# PICO_LCD.net
KiCad netlist of a schematic drawn in Altium Designer
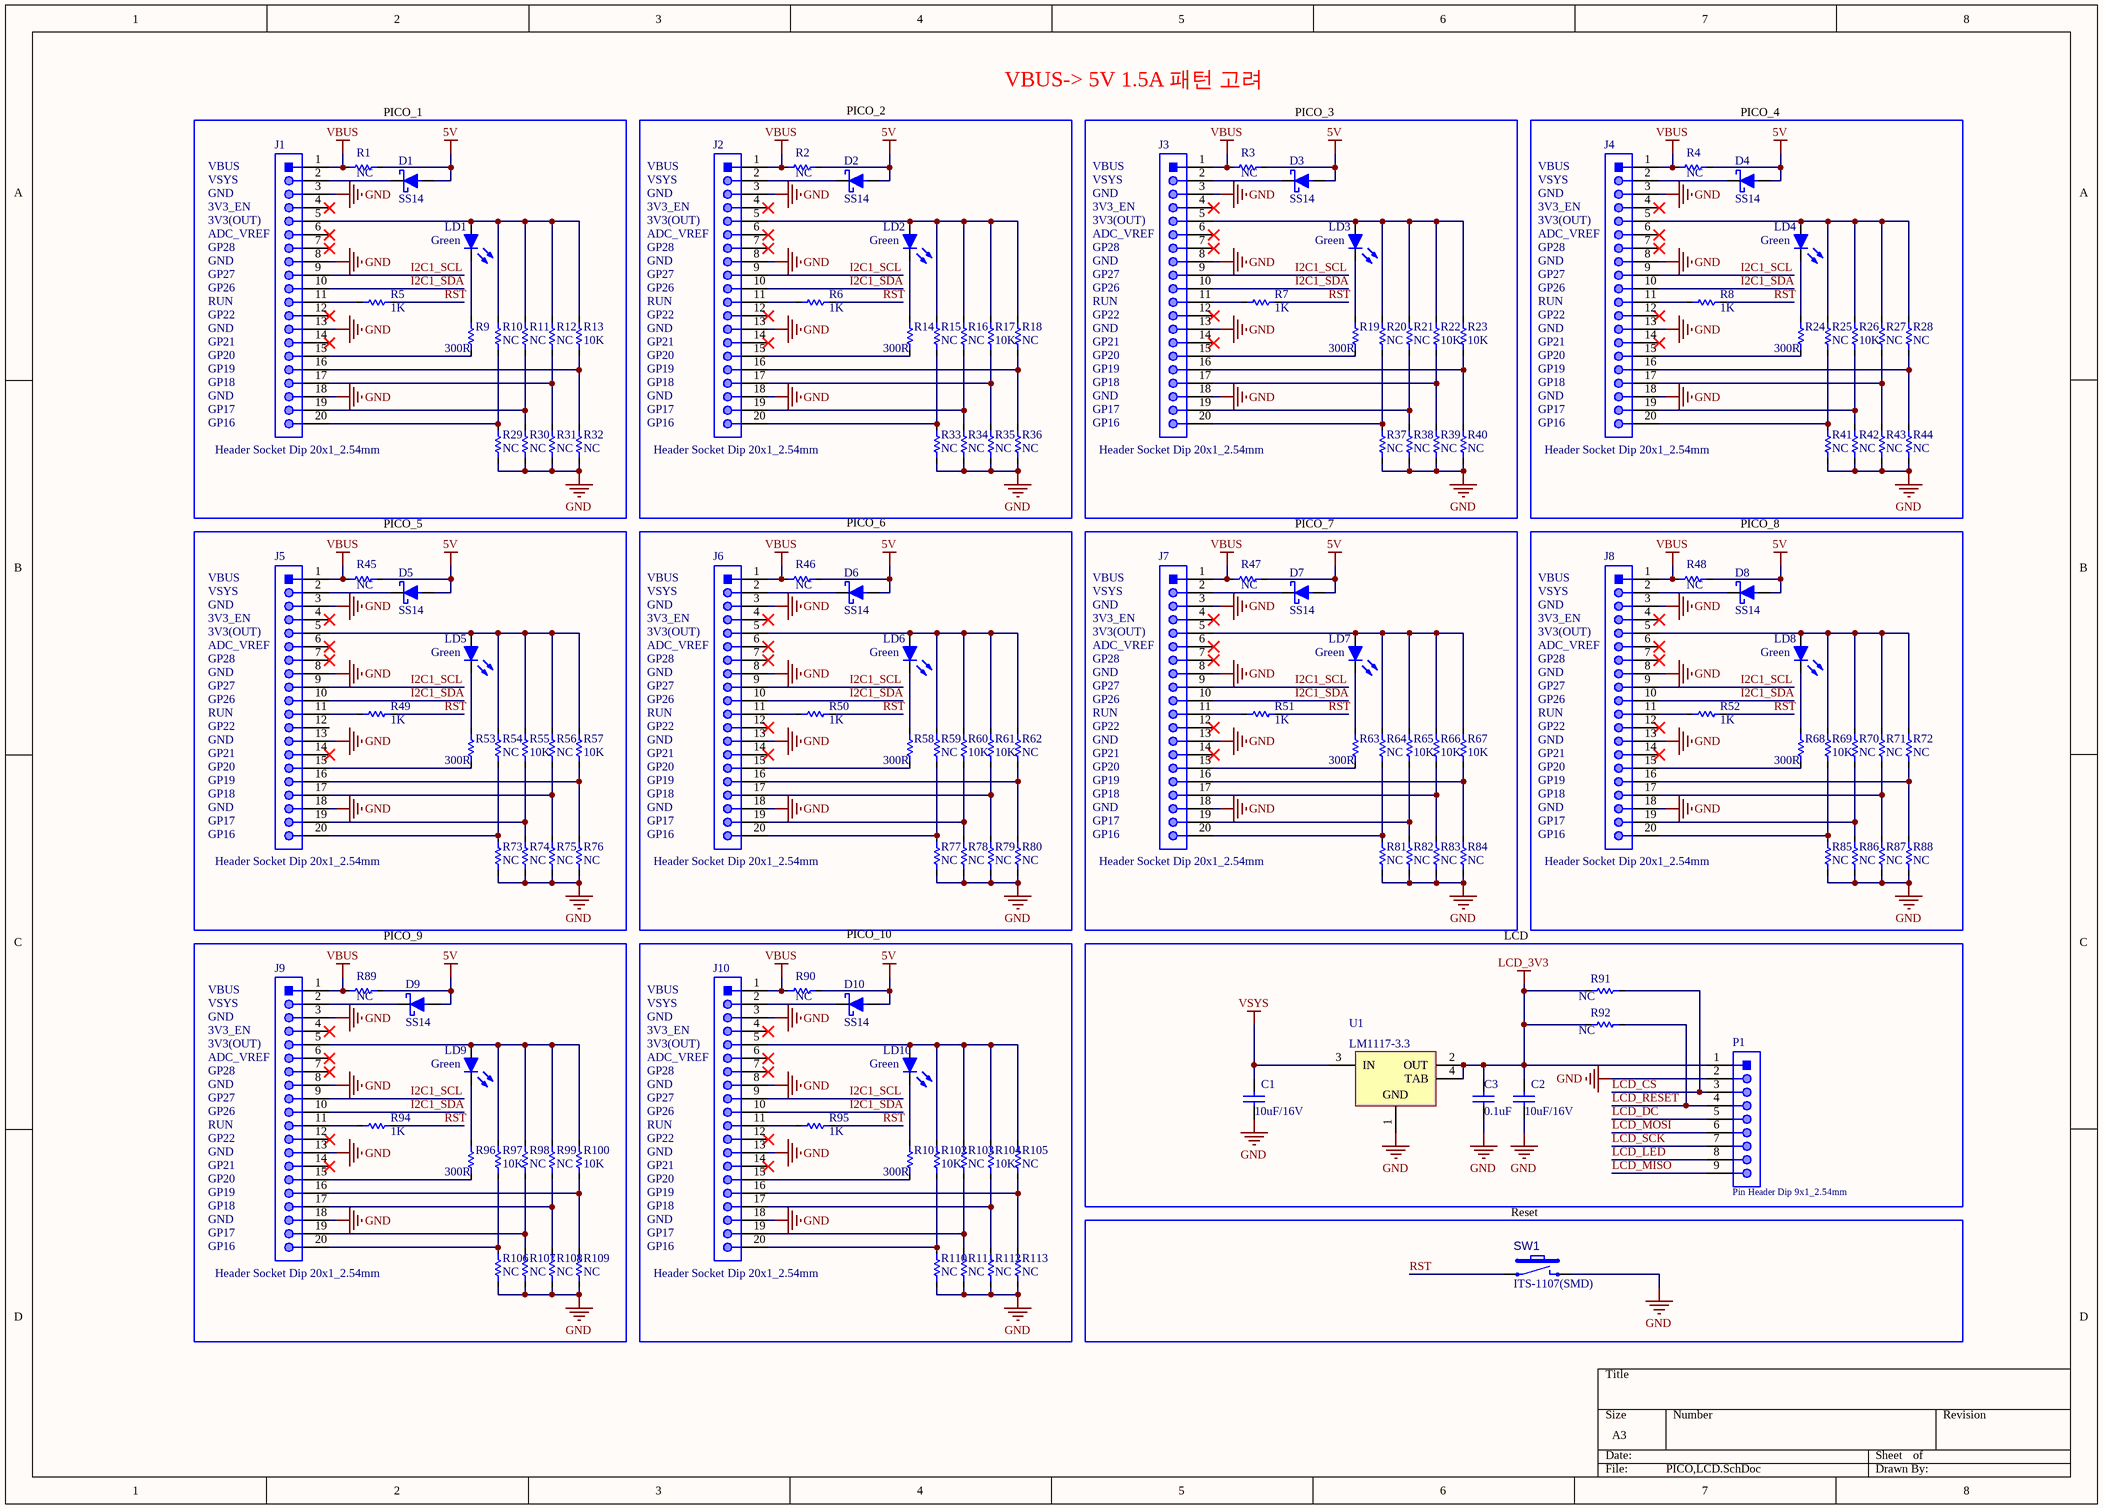
[diagram p0: PICO,LCD.SchDoc]

(export (version "E")
  (design (tool "Eeschema 10.0.6"))
  (components
    (comp (ref "C1")
      (value "10uF/16V")
      (footprint "CAP-0805")
      (description "MLCC-0805(2012)")
      (libsource (lib "Jaden_Lib") (part "CAP-0805"))
    )
    (comp (ref "C2")
      (value "10uF/16V")
      (footprint "CAP-0805")
      (description "MLCC-0805(2012)")
      (libsource (lib "Jaden_Lib") (part "CAP-0805"))
    )
    (comp (ref "C3")
      (value "0.1uF")
      (footprint "CAP-0603")
      (description "MLCC-0603(1608)")
      (libsource (lib "Jaden_Lib") (part "CAP-0603"))
    )
    (comp (ref "D1")
      (value "SS14")
      (footprint "DO-214AC/SMA")
      (description "DIODE SCHOTTKY 40V 1A SMA")
      (fields
        (field (name "MANUFACTURER") "ON Semiconductor")
        (field (name "OCTOPART") "https://octopart.com/ss14-on+semiconductor-29205033")
      )
      (libsource (lib "Jaden_Lib") (part "DIODE-Shottky SMA(DO-214AC)"))
    )
    (comp (ref "D2")
      (value "SS14")
      (footprint "DO-214AC/SMA")
      (description "DIODE SCHOTTKY 40V 1A SMA")
      (fields
        (field (name "MANUFACTURER") "ON Semiconductor")
        (field (name "OCTOPART") "https://octopart.com/ss14-on+semiconductor-29205033")
      )
      (libsource (lib "Jaden_Lib") (part "DIODE-Shottky SMA(DO-214AC)"))
    )
    (comp (ref "D3")
      (value "SS14")
      (footprint "DO-214AC/SMA")
      (description "DIODE SCHOTTKY 40V 1A SMA")
      (fields
        (field (name "MANUFACTURER") "ON Semiconductor")
        (field (name "OCTOPART") "https://octopart.com/ss14-on+semiconductor-29205033")
      )
      (libsource (lib "Jaden_Lib") (part "DIODE-Shottky SMA(DO-214AC)"))
    )
    (comp (ref "D4")
      (value "SS14")
      (footprint "DO-214AC/SMA")
      (description "DIODE SCHOTTKY 40V 1A SMA")
      (fields
        (field (name "MANUFACTURER") "ON Semiconductor")
        (field (name "OCTOPART") "https://octopart.com/ss14-on+semiconductor-29205033")
      )
      (libsource (lib "Jaden_Lib") (part "DIODE-Shottky SMA(DO-214AC)"))
    )
    (comp (ref "D5")
      (value "SS14")
      (footprint "DO-214AC/SMA")
      (description "DIODE SCHOTTKY 40V 1A SMA")
      (fields
        (field (name "MANUFACTURER") "ON Semiconductor")
        (field (name "OCTOPART") "https://octopart.com/ss14-on+semiconductor-29205033")
      )
      (libsource (lib "Jaden_Lib") (part "DIODE-Shottky SMA(DO-214AC)"))
    )
    (comp (ref "D6")
      (value "SS14")
      (footprint "DO-214AC/SMA")
      (description "DIODE SCHOTTKY 40V 1A SMA")
      (fields
        (field (name "MANUFACTURER") "ON Semiconductor")
        (field (name "OCTOPART") "https://octopart.com/ss14-on+semiconductor-29205033")
      )
      (libsource (lib "Jaden_Lib") (part "DIODE-Shottky SMA(DO-214AC)"))
    )
    (comp (ref "D7")
      (value "SS14")
      (footprint "DO-214AC/SMA")
      (description "DIODE SCHOTTKY 40V 1A SMA")
      (fields
        (field (name "MANUFACTURER") "ON Semiconductor")
        (field (name "OCTOPART") "https://octopart.com/ss14-on+semiconductor-29205033")
      )
      (libsource (lib "Jaden_Lib") (part "DIODE-Shottky SMA(DO-214AC)"))
    )
    (comp (ref "D8")
      (value "SS14")
      (footprint "DO-214AC/SMA")
      (description "DIODE SCHOTTKY 40V 1A SMA")
      (fields
        (field (name "MANUFACTURER") "ON Semiconductor")
        (field (name "OCTOPART") "https://octopart.com/ss14-on+semiconductor-29205033")
      )
      (libsource (lib "Jaden_Lib") (part "DIODE-Shottky SMA(DO-214AC)"))
    )
    (comp (ref "D9")
      (value "SS14")
      (footprint "DO-214AC/SMA")
      (description "DIODE SCHOTTKY 40V 1A SMA")
      (fields
        (field (name "MANUFACTURER") "ON Semiconductor")
        (field (name "OCTOPART") "https://octopart.com/ss14-on+semiconductor-29205033")
      )
      (libsource (lib "Jaden_Lib") (part "DIODE-Shottky SMA(DO-214AC)"))
    )
    (comp (ref "D10")
      (value "SS14")
      (footprint "DO-214AC/SMA")
      (description "DIODE SCHOTTKY 40V 1A SMA")
      (fields
        (field (name "MANUFACTURER") "ON Semiconductor")
        (field (name "OCTOPART") "https://octopart.com/ss14-on+semiconductor-29205033")
      )
      (libsource (lib "Jaden_Lib") (part "DIODE-Shottky SMA(DO-214AC)"))
    )
    (comp (ref "J1")
      (value "Header Socket Dip 20x1_2.54mm")
      (footprint "IDC-1X20(SOCKET)")
      (description "THT Vertical Header Socket WR-PHD, Pitch 2.54 mm, Single Row, 20 pins")
      (fields
        (field (name "MANUFACTURER_PART_NUMBER") "M20-7822046")
        (field (name "MOUSER PART NUMBER") "855-M20-7822046")
      )
      (libsource (lib "Jaden_Lib") (part "Header Socket 20x1_2.54mm"))
    )
    (comp (ref "J2")
      (value "Header Socket Dip 20x1_2.54mm")
      (footprint "IDC-1X20(SOCKET)")
      (description "THT Vertical Header Socket WR-PHD, Pitch 2.54 mm, Single Row, 20 pins")
      (fields
        (field (name "MANUFACTURER_PART_NUMBER") "M20-7822046")
        (field (name "MOUSER PART NUMBER") "855-M20-7822046")
      )
      (libsource (lib "Jaden_Lib") (part "Header Socket 20x1_2.54mm"))
    )
    (comp (ref "J3")
      (value "Header Socket Dip 20x1_2.54mm")
      (footprint "IDC-1X20(SOCKET)")
      (description "THT Vertical Header Socket WR-PHD, Pitch 2.54 mm, Single Row, 20 pins")
      (fields
        (field (name "MANUFACTURER_PART_NUMBER") "M20-7822046")
        (field (name "MOUSER PART NUMBER") "855-M20-7822046")
      )
      (libsource (lib "Jaden_Lib") (part "Header Socket 20x1_2.54mm"))
    )
    (comp (ref "J4")
      (value "Header Socket Dip 20x1_2.54mm")
      (footprint "IDC-1X20(SOCKET)")
      (description "THT Vertical Header Socket WR-PHD, Pitch 2.54 mm, Single Row, 20 pins")
      (fields
        (field (name "MANUFACTURER_PART_NUMBER") "M20-7822046")
        (field (name "MOUSER PART NUMBER") "855-M20-7822046")
      )
      (libsource (lib "Jaden_Lib") (part "Header Socket 20x1_2.54mm"))
    )
    (comp (ref "J5")
      (value "Header Socket Dip 20x1_2.54mm")
      (footprint "IDC-1X20(SOCKET)")
      (description "THT Vertical Header Socket WR-PHD, Pitch 2.54 mm, Single Row, 20 pins")
      (fields
        (field (name "MANUFACTURER_PART_NUMBER") "M20-7822046")
        (field (name "MOUSER PART NUMBER") "855-M20-7822046")
      )
      (libsource (lib "Jaden_Lib") (part "Header Socket 20x1_2.54mm"))
    )
    (comp (ref "J6")
      (value "Header Socket Dip 20x1_2.54mm")
      (footprint "IDC-1X20(SOCKET)")
      (description "THT Vertical Header Socket WR-PHD, Pitch 2.54 mm, Single Row, 20 pins")
      (fields
        (field (name "MANUFACTURER_PART_NUMBER") "M20-7822046")
        (field (name "MOUSER PART NUMBER") "855-M20-7822046")
      )
      (libsource (lib "Jaden_Lib") (part "Header Socket 20x1_2.54mm"))
    )
    (comp (ref "J7")
      (value "Header Socket Dip 20x1_2.54mm")
      (footprint "IDC-1X20(SOCKET)")
      (description "THT Vertical Header Socket WR-PHD, Pitch 2.54 mm, Single Row, 20 pins")
      (fields
        (field (name "MANUFACTURER_PART_NUMBER") "M20-7822046")
        (field (name "MOUSER PART NUMBER") "855-M20-7822046")
      )
      (libsource (lib "Jaden_Lib") (part "Header Socket 20x1_2.54mm"))
    )
    (comp (ref "J8")
      (value "Header Socket Dip 20x1_2.54mm")
      (footprint "IDC-1X20(SOCKET)")
      (description "THT Vertical Header Socket WR-PHD, Pitch 2.54 mm, Single Row, 20 pins")
      (fields
        (field (name "MANUFACTURER_PART_NUMBER") "M20-7822046")
        (field (name "MOUSER PART NUMBER") "855-M20-7822046")
      )
      (libsource (lib "Jaden_Lib") (part "Header Socket 20x1_2.54mm"))
    )
    (comp (ref "J9")
      (value "Header Socket Dip 20x1_2.54mm")
      (footprint "IDC-1X20(SOCKET)")
      (description "THT Vertical Header Socket WR-PHD, Pitch 2.54 mm, Single Row, 20 pins")
      (fields
        (field (name "MANUFACTURER_PART_NUMBER") "M20-7822046")
        (field (name "MOUSER PART NUMBER") "855-M20-7822046")
      )
      (libsource (lib "Jaden_Lib") (part "Header Socket 20x1_2.54mm"))
    )
    (comp (ref "J10")
      (value "Header Socket Dip 20x1_2.54mm")
      (footprint "IDC-1X20(SOCKET)")
      (description "THT Vertical Header Socket WR-PHD, Pitch 2.54 mm, Single Row, 20 pins")
      (fields
        (field (name "MANUFACTURER_PART_NUMBER") "M20-7822046")
        (field (name "MOUSER PART NUMBER") "855-M20-7822046")
      )
      (libsource (lib "Jaden_Lib") (part "Header Socket 20x1_2.54mm"))
    )
    (comp (ref "LD1")
      (value "Green")
      (footprint "LED-0603-GREEN")
      (description "LED-0603")
      (libsource (lib "Jaden_Lib") (part "GREEN LED-0603"))
    )
    (comp (ref "LD2")
      (value "Green")
      (footprint "LED-0603-GREEN")
      (description "LED-0603")
      (libsource (lib "Jaden_Lib") (part "GREEN LED-0603"))
    )
    (comp (ref "LD3")
      (value "Green")
      (footprint "LED-0603-GREEN")
      (description "LED-0603")
      (libsource (lib "Jaden_Lib") (part "GREEN LED-0603"))
    )
    (comp (ref "LD4")
      (value "Green")
      (footprint "LED-0603-GREEN")
      (description "LED-0603")
      (libsource (lib "Jaden_Lib") (part "GREEN LED-0603"))
    )
    (comp (ref "LD5")
      (value "Green")
      (footprint "LED-0603-GREEN")
      (description "LED-0603")
      (libsource (lib "Jaden_Lib") (part "GREEN LED-0603"))
    )
    (comp (ref "LD6")
      (value "Green")
      (footprint "LED-0603-GREEN")
      (description "LED-0603")
      (libsource (lib "Jaden_Lib") (part "GREEN LED-0603"))
    )
    (comp (ref "LD7")
      (value "Green")
      (footprint "LED-0603-GREEN")
      (description "LED-0603")
      (libsource (lib "Jaden_Lib") (part "GREEN LED-0603"))
    )
    (comp (ref "LD8")
      (value "Green")
      (footprint "LED-0603-GREEN")
      (description "LED-0603")
      (libsource (lib "Jaden_Lib") (part "GREEN LED-0603"))
    )
    (comp (ref "LD9")
      (value "Green")
      (footprint "LED-0603-GREEN")
      (description "LED-0603")
      (libsource (lib "Jaden_Lib") (part "GREEN LED-0603"))
    )
    (comp (ref "LD10")
      (value "Green")
      (footprint "LED-0603-GREEN")
      (description "LED-0603")
      (libsource (lib "Jaden_Lib") (part "GREEN LED-0603"))
    )
    (comp (ref "P1")
      (value "Pin Header Dip 9x1_2.54mm")
      (footprint "LCD(PIN HEADER9X1_2.54)")
      (description "THT Vertical Pin Header WR-PHD, Pitch 2.54 mm, Single Row, 9 pins")
      (fields
        (field (name "PART NUMBER") "61300911121")
        (field (name "MANUFACTURER") "Wurth Elektronik")
        (field (name "PUBLISHER") "WurthElektronik")
      )
      (libsource (lib "Jaden_Lib") (part "Pin Header 9x1_2.54mm"))
    )
    (comp (ref "R1")
      (value "NC")
      (footprint "RES-0603")
      (description "Chip Resistor 0603(1608)")
      (fields (field (name "TOLERANCE") "1%") (field (name "MANUFACTURER") "Yageo"))
      (libsource (lib "Jaden_Lib") (part "RES-0603"))
    )
    (comp (ref "R2")
      (value "NC")
      (footprint "RES-0603")
      (description "Chip Resistor 0603(1608)")
      (fields (field (name "TOLERANCE") "1%") (field (name "MANUFACTURER") "Yageo"))
      (libsource (lib "Jaden_Lib") (part "RES-0603"))
    )
    (comp (ref "R3")
      (value "NC")
      (footprint "RES-0603")
      (description "Chip Resistor 0603(1608)")
      (fields (field (name "TOLERANCE") "1%") (field (name "MANUFACTURER") "Yageo"))
      (libsource (lib "Jaden_Lib") (part "RES-0603"))
    )
    (comp (ref "R4")
      (value "NC")
      (footprint "RES-0603")
      (description "Chip Resistor 0603(1608)")
      (fields (field (name "TOLERANCE") "1%") (field (name "MANUFACTURER") "Yageo"))
      (libsource (lib "Jaden_Lib") (part "RES-0603"))
    )
    (comp (ref "R5")
      (value "1K")
      (footprint "RES-0603")
      (description "Chip Resistor 0603(1608)")
      (fields (field (name "TOLERANCE") "1%") (field (name "MANUFACTURER") "Yageo"))
      (libsource (lib "Jaden_Lib") (part "RES-0603"))
    )
    (comp (ref "R6")
      (value "1K")
      (footprint "RES-0603")
      (description "Chip Resistor 0603(1608)")
      (fields (field (name "TOLERANCE") "1%") (field (name "MANUFACTURER") "Yageo"))
      (libsource (lib "Jaden_Lib") (part "RES-0603"))
    )
    (comp (ref "R7")
      (value "1K")
      (footprint "RES-0603")
      (description "Chip Resistor 0603(1608)")
      (fields (field (name "TOLERANCE") "1%") (field (name "MANUFACTURER") "Yageo"))
      (libsource (lib "Jaden_Lib") (part "RES-0603"))
    )
    (comp (ref "R8")
      (value "1K")
      (footprint "RES-0603")
      (description "Chip Resistor 0603(1608)")
      (fields (field (name "TOLERANCE") "1%") (field (name "MANUFACTURER") "Yageo"))
      (libsource (lib "Jaden_Lib") (part "RES-0603"))
    )
    (comp (ref "R9")
      (value "300R")
      (footprint "RES-0603")
      (description "Chip Resistor 0603(1608)")
      (fields (field (name "TOLERANCE") "1%") (field (name "MANUFACTURER") "Yageo"))
      (libsource (lib "Jaden_Lib") (part "RES-0603"))
    )
    (comp (ref "R10")
      (value "NC")
      (footprint "RES-0603")
      (description "Chip Resistor 0603(1608)")
      (fields (field (name "TOLERANCE") "1%") (field (name "MANUFACTURER") "Yageo"))
      (libsource (lib "Jaden_Lib") (part "RES-0603"))
    )
    (comp (ref "R11")
      (value "NC")
      (footprint "RES-0603")
      (description "Chip Resistor 0603(1608)")
      (fields (field (name "TOLERANCE") "1%") (field (name "MANUFACTURER") "Yageo"))
      (libsource (lib "Jaden_Lib") (part "RES-0603"))
    )
    (comp (ref "R12")
      (value "NC")
      (footprint "RES-0603")
      (description "Chip Resistor 0603(1608)")
      (fields (field (name "TOLERANCE") "1%") (field (name "MANUFACTURER") "Yageo"))
      (libsource (lib "Jaden_Lib") (part "RES-0603"))
    )
    (comp (ref "R13")
      (value "10K")
      (footprint "RES-0603")
      (description "Chip Resistor 0603(1608)")
      (fields (field (name "TOLERANCE") "1%") (field (name "MANUFACTURER") "Yageo"))
      (libsource (lib "Jaden_Lib") (part "RES-0603"))
    )
    (comp (ref "R14")
      (value "300R")
      (footprint "RES-0603")
      (description "Chip Resistor 0603(1608)")
      (fields (field (name "TOLERANCE") "1%") (field (name "MANUFACTURER") "Yageo"))
      (libsource (lib "Jaden_Lib") (part "RES-0603"))
    )
    (comp (ref "R15")
      (value "NC")
      (footprint "RES-0603")
      (description "Chip Resistor 0603(1608)")
      (fields (field (name "TOLERANCE") "1%") (field (name "MANUFACTURER") "Yageo"))
      (libsource (lib "Jaden_Lib") (part "RES-0603"))
    )
    (comp (ref "R16")
      (value "NC")
      (footprint "RES-0603")
      (description "Chip Resistor 0603(1608)")
      (fields (field (name "TOLERANCE") "1%") (field (name "MANUFACTURER") "Yageo"))
      (libsource (lib "Jaden_Lib") (part "RES-0603"))
    )
    (comp (ref "R17")
      (value "10K")
      (footprint "RES-0603")
      (description "Chip Resistor 0603(1608)")
      (fields (field (name "TOLERANCE") "1%") (field (name "MANUFACTURER") "Yageo"))
      (libsource (lib "Jaden_Lib") (part "RES-0603"))
    )
    (comp (ref "R18")
      (value "NC")
      (footprint "RES-0603")
      (description "Chip Resistor 0603(1608)")
      (fields (field (name "TOLERANCE") "1%") (field (name "MANUFACTURER") "Yageo"))
      (libsource (lib "Jaden_Lib") (part "RES-0603"))
    )
    (comp (ref "R19")
      (value "300R")
      (footprint "RES-0603")
      (description "Chip Resistor 0603(1608)")
      (fields (field (name "TOLERANCE") "1%") (field (name "MANUFACTURER") "Yageo"))
      (libsource (lib "Jaden_Lib") (part "RES-0603"))
    )
    (comp (ref "R20")
      (value "NC")
      (footprint "RES-0603")
      (description "Chip Resistor 0603(1608)")
      (fields (field (name "TOLERANCE") "1%") (field (name "MANUFACTURER") "Yageo"))
      (libsource (lib "Jaden_Lib") (part "RES-0603"))
    )
    (comp (ref "R21")
      (value "NC")
      (footprint "RES-0603")
      (description "Chip Resistor 0603(1608)")
      (fields (field (name "TOLERANCE") "1%") (field (name "MANUFACTURER") "Yageo"))
      (libsource (lib "Jaden_Lib") (part "RES-0603"))
    )
    (comp (ref "R22")
      (value "10K")
      (footprint "RES-0603")
      (description "Chip Resistor 0603(1608)")
      (fields (field (name "TOLERANCE") "1%") (field (name "MANUFACTURER") "Yageo"))
      (libsource (lib "Jaden_Lib") (part "RES-0603"))
    )
    (comp (ref "R23")
      (value "10K")
      (footprint "RES-0603")
      (description "Chip Resistor 0603(1608)")
      (fields (field (name "TOLERANCE") "1%") (field (name "MANUFACTURER") "Yageo"))
      (libsource (lib "Jaden_Lib") (part "RES-0603"))
    )
    (comp (ref "R24")
      (value "300R")
      (footprint "RES-0603")
      (description "Chip Resistor 0603(1608)")
      (fields (field (name "TOLERANCE") "1%") (field (name "MANUFACTURER") "Yageo"))
      (libsource (lib "Jaden_Lib") (part "RES-0603"))
    )
    (comp (ref "R25")
      (value "NC")
      (footprint "RES-0603")
      (description "Chip Resistor 0603(1608)")
      (fields (field (name "TOLERANCE") "1%") (field (name "MANUFACTURER") "Yageo"))
      (libsource (lib "Jaden_Lib") (part "RES-0603"))
    )
    (comp (ref "R26")
      (value "10K")
      (footprint "RES-0603")
      (description "Chip Resistor 0603(1608)")
      (fields (field (name "TOLERANCE") "1%") (field (name "MANUFACTURER") "Yageo"))
      (libsource (lib "Jaden_Lib") (part "RES-0603"))
    )
    (comp (ref "R27")
      (value "NC")
      (footprint "RES-0603")
      (description "Chip Resistor 0603(1608)")
      (fields (field (name "TOLERANCE") "1%") (field (name "MANUFACTURER") "Yageo"))
      (libsource (lib "Jaden_Lib") (part "RES-0603"))
    )
    (comp (ref "R28")
      (value "NC")
      (footprint "RES-0603")
      (description "Chip Resistor 0603(1608)")
      (fields (field (name "TOLERANCE") "1%") (field (name "MANUFACTURER") "Yageo"))
      (libsource (lib "Jaden_Lib") (part "RES-0603"))
    )
    (comp (ref "R29")
      (value "NC")
      (footprint "RES-0603")
      (description "Chip Resistor 0603(1608)")
      (fields (field (name "TOLERANCE") "1%") (field (name "MANUFACTURER") "Yageo"))
      (libsource (lib "Jaden_Lib") (part "RES-0603"))
    )
    (comp (ref "R30")
      (value "NC")
      (footprint "RES-0603")
      (description "Chip Resistor 0603(1608)")
      (fields (field (name "TOLERANCE") "1%") (field (name "MANUFACTURER") "Yageo"))
      (libsource (lib "Jaden_Lib") (part "RES-0603"))
    )
    (comp (ref "R31")
      (value "NC")
      (footprint "RES-0603")
      (description "Chip Resistor 0603(1608)")
      (fields (field (name "TOLERANCE") "1%") (field (name "MANUFACTURER") "Yageo"))
      (libsource (lib "Jaden_Lib") (part "RES-0603"))
    )
    (comp (ref "R32")
      (value "NC")
      (footprint "RES-0603")
      (description "Chip Resistor 0603(1608)")
      (fields (field (name "TOLERANCE") "1%") (field (name "MANUFACTURER") "Yageo"))
      (libsource (lib "Jaden_Lib") (part "RES-0603"))
    )
    (comp (ref "R33")
      (value "NC")
      (footprint "RES-0603")
      (description "Chip Resistor 0603(1608)")
      (fields (field (name "TOLERANCE") "1%") (field (name "MANUFACTURER") "Yageo"))
      (libsource (lib "Jaden_Lib") (part "RES-0603"))
    )
    (comp (ref "R34")
      (value "NC")
      (footprint "RES-0603")
      (description "Chip Resistor 0603(1608)")
      (fields (field (name "TOLERANCE") "1%") (field (name "MANUFACTURER") "Yageo"))
      (libsource (lib "Jaden_Lib") (part "RES-0603"))
    )
    (comp (ref "R35")
      (value "NC")
      (footprint "RES-0603")
      (description "Chip Resistor 0603(1608)")
      (fields (field (name "TOLERANCE") "1%") (field (name "MANUFACTURER") "Yageo"))
      (libsource (lib "Jaden_Lib") (part "RES-0603"))
    )
    (comp (ref "R36")
      (value "NC")
      (footprint "RES-0603")
      (description "Chip Resistor 0603(1608)")
      (fields (field (name "TOLERANCE") "1%") (field (name "MANUFACTURER") "Yageo"))
      (libsource (lib "Jaden_Lib") (part "RES-0603"))
    )
    (comp (ref "R37")
      (value "NC")
      (footprint "RES-0603")
      (description "Chip Resistor 0603(1608)")
      (fields (field (name "TOLERANCE") "1%") (field (name "MANUFACTURER") "Yageo"))
      (libsource (lib "Jaden_Lib") (part "RES-0603"))
    )
    (comp (ref "R38")
      (value "NC")
      (footprint "RES-0603")
      (description "Chip Resistor 0603(1608)")
      (fields (field (name "TOLERANCE") "1%") (field (name "MANUFACTURER") "Yageo"))
      (libsource (lib "Jaden_Lib") (part "RES-0603"))
    )
    (comp (ref "R39")
      (value "NC")
      (footprint "RES-0603")
      (description "Chip Resistor 0603(1608)")
      (fields (field (name "TOLERANCE") "1%") (field (name "MANUFACTURER") "Yageo"))
      (libsource (lib "Jaden_Lib") (part "RES-0603"))
    )
    (comp (ref "R40")
      (value "NC")
      (footprint "RES-0603")
      (description "Chip Resistor 0603(1608)")
      (fields (field (name "TOLERANCE") "1%") (field (name "MANUFACTURER") "Yageo"))
      (libsource (lib "Jaden_Lib") (part "RES-0603"))
    )
    (comp (ref "R41")
      (value "NC")
      (footprint "RES-0603")
      (description "Chip Resistor 0603(1608)")
      (fields (field (name "TOLERANCE") "1%") (field (name "MANUFACTURER") "Yageo"))
      (libsource (lib "Jaden_Lib") (part "RES-0603"))
    )
    (comp (ref "R42")
      (value "NC")
      (footprint "RES-0603")
      (description "Chip Resistor 0603(1608)")
      (fields (field (name "TOLERANCE") "1%") (field (name "MANUFACTURER") "Yageo"))
      (libsource (lib "Jaden_Lib") (part "RES-0603"))
    )
    (comp (ref "R43")
      (value "NC")
      (footprint "RES-0603")
      (description "Chip Resistor 0603(1608)")
      (fields (field (name "TOLERANCE") "1%") (field (name "MANUFACTURER") "Yageo"))
      (libsource (lib "Jaden_Lib") (part "RES-0603"))
    )
    (comp (ref "R44")
      (value "NC")
      (footprint "RES-0603")
      (description "Chip Resistor 0603(1608)")
      (fields (field (name "TOLERANCE") "1%") (field (name "MANUFACTURER") "Yageo"))
      (libsource (lib "Jaden_Lib") (part "RES-0603"))
    )
    (comp (ref "R45")
      (value "NC")
      (footprint "RES-0603")
      (description "Chip Resistor 0603(1608)")
      (fields (field (name "TOLERANCE") "1%") (field (name "MANUFACTURER") "Yageo"))
      (libsource (lib "Jaden_Lib") (part "RES-0603"))
    )
    (comp (ref "R46")
      (value "NC")
      (footprint "RES-0603")
      (description "Chip Resistor 0603(1608)")
      (fields (field (name "TOLERANCE") "1%") (field (name "MANUFACTURER") "Yageo"))
      (libsource (lib "Jaden_Lib") (part "RES-0603"))
    )
    (comp (ref "R47")
      (value "NC")
      (footprint "RES-0603")
      (description "Chip Resistor 0603(1608)")
      (fields (field (name "TOLERANCE") "1%") (field (name "MANUFACTURER") "Yageo"))
      (libsource (lib "Jaden_Lib") (part "RES-0603"))
    )
    (comp (ref "R48")
      (value "NC")
      (footprint "RES-0603")
      (description "Chip Resistor 0603(1608)")
      (fields (field (name "TOLERANCE") "1%") (field (name "MANUFACTURER") "Yageo"))
      (libsource (lib "Jaden_Lib") (part "RES-0603"))
    )
    (comp (ref "R49")
      (value "1K")
      (footprint "RES-0603")
      (description "Chip Resistor 0603(1608)")
      (fields (field (name "TOLERANCE") "1%") (field (name "MANUFACTURER") "Yageo"))
      (libsource (lib "Jaden_Lib") (part "RES-0603"))
    )
    (comp (ref "R50")
      (value "1K")
      (footprint "RES-0603")
      (description "Chip Resistor 0603(1608)")
      (fields (field (name "TOLERANCE") "1%") (field (name "MANUFACTURER") "Yageo"))
      (libsource (lib "Jaden_Lib") (part "RES-0603"))
    )
    (comp (ref "R51")
      (value "1K")
      (footprint "RES-0603")
      (description "Chip Resistor 0603(1608)")
      (fields (field (name "TOLERANCE") "1%") (field (name "MANUFACTURER") "Yageo"))
      (libsource (lib "Jaden_Lib") (part "RES-0603"))
    )
    (comp (ref "R52")
      (value "1K")
      (footprint "RES-0603")
      (description "Chip Resistor 0603(1608)")
      (fields (field (name "TOLERANCE") "1%") (field (name "MANUFACTURER") "Yageo"))
      (libsource (lib "Jaden_Lib") (part "RES-0603"))
    )
    (comp (ref "R53")
      (value "300R")
      (footprint "RES-0603")
      (description "Chip Resistor 0603(1608)")
      (fields (field (name "TOLERANCE") "1%") (field (name "MANUFACTURER") "Yageo"))
      (libsource (lib "Jaden_Lib") (part "RES-0603"))
    )
    (comp (ref "R54")
      (value "NC")
      (footprint "RES-0603")
      (description "Chip Resistor 0603(1608)")
      (fields (field (name "TOLERANCE") "1%") (field (name "MANUFACTURER") "Yageo"))
      (libsource (lib "Jaden_Lib") (part "RES-0603"))
    )
    (comp (ref "R55")
      (value "10K")
      (footprint "RES-0603")
      (description "Chip Resistor 0603(1608)")
      (fields (field (name "TOLERANCE") "1%") (field (name "MANUFACTURER") "Yageo"))
      (libsource (lib "Jaden_Lib") (part "RES-0603"))
    )
    (comp (ref "R56")
      (value "NC")
      (footprint "RES-0603")
      (description "Chip Resistor 0603(1608)")
      (fields (field (name "TOLERANCE") "1%") (field (name "MANUFACTURER") "Yageo"))
      (libsource (lib "Jaden_Lib") (part "RES-0603"))
    )
    (comp (ref "R57")
      (value "10K")
      (footprint "RES-0603")
      (description "Chip Resistor 0603(1608)")
      (fields (field (name "TOLERANCE") "1%") (field (name "MANUFACTURER") "Yageo"))
      (libsource (lib "Jaden_Lib") (part "RES-0603"))
    )
    (comp (ref "R58")
      (value "300R")
      (footprint "RES-0603")
      (description "Chip Resistor 0603(1608)")
      (fields (field (name "TOLERANCE") "1%") (field (name "MANUFACTURER") "Yageo"))
      (libsource (lib "Jaden_Lib") (part "RES-0603"))
    )
    (comp (ref "R59")
      (value "NC")
      (footprint "RES-0603")
      (description "Chip Resistor 0603(1608)")
      (fields (field (name "TOLERANCE") "1%") (field (name "MANUFACTURER") "Yageo"))
      (libsource (lib "Jaden_Lib") (part "RES-0603"))
    )
    (comp (ref "R60")
      (value "10K")
      (footprint "RES-0603")
      (description "Chip Resistor 0603(1608)")
      (fields (field (name "TOLERANCE") "1%") (field (name "MANUFACTURER") "Yageo"))
      (libsource (lib "Jaden_Lib") (part "RES-0603"))
    )
    (comp (ref "R61")
      (value "10K")
      (footprint "RES-0603")
      (description "Chip Resistor 0603(1608)")
      (fields (field (name "TOLERANCE") "1%") (field (name "MANUFACTURER") "Yageo"))
      (libsource (lib "Jaden_Lib") (part "RES-0603"))
    )
    (comp (ref "R62")
      (value "NC")
      (footprint "RES-0603")
      (description "Chip Resistor 0603(1608)")
      (fields (field (name "TOLERANCE") "1%") (field (name "MANUFACTURER") "Yageo"))
      (libsource (lib "Jaden_Lib") (part "RES-0603"))
    )
    (comp (ref "R63")
      (value "300R")
      (footprint "RES-0603")
      (description "Chip Resistor 0603(1608)")
      (fields (field (name "TOLERANCE") "1%") (field (name "MANUFACTURER") "Yageo"))
      (libsource (lib "Jaden_Lib") (part "RES-0603"))
    )
    (comp (ref "R64")
      (value "NC")
      (footprint "RES-0603")
      (description "Chip Resistor 0603(1608)")
      (fields (field (name "TOLERANCE") "1%") (field (name "MANUFACTURER") "Yageo"))
      (libsource (lib "Jaden_Lib") (part "RES-0603"))
    )
    (comp (ref "R65")
      (value "10K")
      (footprint "RES-0603")
      (description "Chip Resistor 0603(1608)")
      (fields (field (name "TOLERANCE") "1%") (field (name "MANUFACTURER") "Yageo"))
      (libsource (lib "Jaden_Lib") (part "RES-0603"))
    )
    (comp (ref "R66")
      (value "10K")
      (footprint "RES-0603")
      (description "Chip Resistor 0603(1608)")
      (fields (field (name "TOLERANCE") "1%") (field (name "MANUFACTURER") "Yageo"))
      (libsource (lib "Jaden_Lib") (part "RES-0603"))
    )
    (comp (ref "R67")
      (value "10K")
      (footprint "RES-0603")
      (description "Chip Resistor 0603(1608)")
      (fields (field (name "TOLERANCE") "1%") (field (name "MANUFACTURER") "Yageo"))
      (libsource (lib "Jaden_Lib") (part "RES-0603"))
    )
    (comp (ref "R68")
      (value "300R")
      (footprint "RES-0603")
      (description "Chip Resistor 0603(1608)")
      (fields (field (name "TOLERANCE") "1%") (field (name "MANUFACTURER") "Yageo"))
      (libsource (lib "Jaden_Lib") (part "RES-0603"))
    )
    (comp (ref "R69")
      (value "10K")
      (footprint "RES-0603")
      (description "Chip Resistor 0603(1608)")
      (fields (field (name "TOLERANCE") "1%") (field (name "MANUFACTURER") "Yageo"))
      (libsource (lib "Jaden_Lib") (part "RES-0603"))
    )
    (comp (ref "R70")
      (value "NC")
      (footprint "RES-0603")
      (description "Chip Resistor 0603(1608)")
      (fields (field (name "TOLERANCE") "1%") (field (name "MANUFACTURER") "Yageo"))
      (libsource (lib "Jaden_Lib") (part "RES-0603"))
    )
    (comp (ref "R71")
      (value "NC")
      (footprint "RES-0603")
      (description "Chip Resistor 0603(1608)")
      (fields (field (name "TOLERANCE") "1%") (field (name "MANUFACTURER") "Yageo"))
      (libsource (lib "Jaden_Lib") (part "RES-0603"))
    )
    (comp (ref "R72")
      (value "NC")
      (footprint "RES-0603")
      (description "Chip Resistor 0603(1608)")
      (fields (field (name "TOLERANCE") "1%") (field (name "MANUFACTURER") "Yageo"))
      (libsource (lib "Jaden_Lib") (part "RES-0603"))
    )
    (comp (ref "R73")
      (value "NC")
      (footprint "RES-0603")
      (description "Chip Resistor 0603(1608)")
      (fields (field (name "TOLERANCE") "1%") (field (name "MANUFACTURER") "Yageo"))
      (libsource (lib "Jaden_Lib") (part "RES-0603"))
    )
    (comp (ref "R74")
      (value "NC")
      (footprint "RES-0603")
      (description "Chip Resistor 0603(1608)")
      (fields (field (name "TOLERANCE") "1%") (field (name "MANUFACTURER") "Yageo"))
      (libsource (lib "Jaden_Lib") (part "RES-0603"))
    )
    (comp (ref "R75")
      (value "NC")
      (footprint "RES-0603")
      (description "Chip Resistor 0603(1608)")
      (fields (field (name "TOLERANCE") "1%") (field (name "MANUFACTURER") "Yageo"))
      (libsource (lib "Jaden_Lib") (part "RES-0603"))
    )
    (comp (ref "R76")
      (value "NC")
      (footprint "RES-0603")
      (description "Chip Resistor 0603(1608)")
      (fields (field (name "TOLERANCE") "1%") (field (name "MANUFACTURER") "Yageo"))
      (libsource (lib "Jaden_Lib") (part "RES-0603"))
    )
    (comp (ref "R77")
      (value "NC")
      (footprint "RES-0603")
      (description "Chip Resistor 0603(1608)")
      (fields (field (name "TOLERANCE") "1%") (field (name "MANUFACTURER") "Yageo"))
      (libsource (lib "Jaden_Lib") (part "RES-0603"))
    )
    (comp (ref "R78")
      (value "NC")
      (footprint "RES-0603")
      (description "Chip Resistor 0603(1608)")
      (fields (field (name "TOLERANCE") "1%") (field (name "MANUFACTURER") "Yageo"))
      (libsource (lib "Jaden_Lib") (part "RES-0603"))
    )
    (comp (ref "R79")
      (value "NC")
      (footprint "RES-0603")
      (description "Chip Resistor 0603(1608)")
      (fields (field (name "TOLERANCE") "1%") (field (name "MANUFACTURER") "Yageo"))
      (libsource (lib "Jaden_Lib") (part "RES-0603"))
    )
    (comp (ref "R80")
      (value "NC")
      (footprint "RES-0603")
      (description "Chip Resistor 0603(1608)")
      (fields (field (name "TOLERANCE") "1%") (field (name "MANUFACTURER") "Yageo"))
      (libsource (lib "Jaden_Lib") (part "RES-0603"))
    )
    (comp (ref "R81")
      (value "NC")
      (footprint "RES-0603")
      (description "Chip Resistor 0603(1608)")
      (fields (field (name "TOLERANCE") "1%") (field (name "MANUFACTURER") "Yageo"))
      (libsource (lib "Jaden_Lib") (part "RES-0603"))
    )
    (comp (ref "R82")
      (value "NC")
      (footprint "RES-0603")
      (description "Chip Resistor 0603(1608)")
      (fields (field (name "TOLERANCE") "1%") (field (name "MANUFACTURER") "Yageo"))
      (libsource (lib "Jaden_Lib") (part "RES-0603"))
    )
    (comp (ref "R83")
      (value "NC")
      (footprint "RES-0603")
      (description "Chip Resistor 0603(1608)")
      (fields (field (name "TOLERANCE") "1%") (field (name "MANUFACTURER") "Yageo"))
      (libsource (lib "Jaden_Lib") (part "RES-0603"))
    )
    (comp (ref "R84")
      (value "NC")
      (footprint "RES-0603")
      (description "Chip Resistor 0603(1608)")
      (fields (field (name "TOLERANCE") "1%") (field (name "MANUFACTURER") "Yageo"))
      (libsource (lib "Jaden_Lib") (part "RES-0603"))
    )
    (comp (ref "R85")
      (value "NC")
      (footprint "RES-0603")
      (description "Chip Resistor 0603(1608)")
      (fields (field (name "TOLERANCE") "1%") (field (name "MANUFACTURER") "Yageo"))
      (libsource (lib "Jaden_Lib") (part "RES-0603"))
    )
    (comp (ref "R86")
      (value "NC")
      (footprint "RES-0603")
      (description "Chip Resistor 0603(1608)")
      (fields (field (name "TOLERANCE") "1%") (field (name "MANUFACTURER") "Yageo"))
      (libsource (lib "Jaden_Lib") (part "RES-0603"))
    )
    (comp (ref "R87")
      (value "NC")
      (footprint "RES-0603")
      (description "Chip Resistor 0603(1608)")
      (fields (field (name "TOLERANCE") "1%") (field (name "MANUFACTURER") "Yageo"))
      (libsource (lib "Jaden_Lib") (part "RES-0603"))
    )
    (comp (ref "R88")
      (value "NC")
      (footprint "RES-0603")
      (description "Chip Resistor 0603(1608)")
      (fields (field (name "TOLERANCE") "1%") (field (name "MANUFACTURER") "Yageo"))
      (libsource (lib "Jaden_Lib") (part "RES-0603"))
    )
    (comp (ref "R89")
      (value "NC")
      (footprint "RES-0603")
      (description "Chip Resistor 0603(1608)")
      (fields (field (name "TOLERANCE") "1%") (field (name "MANUFACTURER") "Yageo"))
      (libsource (lib "Jaden_Lib") (part "RES-0603"))
    )
    (comp (ref "R90")
      (value "NC")
      (footprint "RES-0603")
      (description "Chip Resistor 0603(1608)")
      (fields (field (name "TOLERANCE") "1%") (field (name "MANUFACTURER") "Yageo"))
      (libsource (lib "Jaden_Lib") (part "RES-0603"))
    )
    (comp (ref "R91")
      (value "NC")
      (footprint "RES-0603")
      (description "Chip Resistor 0603(1608)")
      (fields (field (name "TOLERANCE") "1%") (field (name "MANUFACTURER") "Yageo"))
      (libsource (lib "Jaden_Lib") (part "RES-0603"))
    )
    (comp (ref "R92")
      (value "NC")
      (footprint "RES-0603")
      (description "Chip Resistor 0603(1608)")
      (fields (field (name "TOLERANCE") "1%") (field (name "MANUFACTURER") "Yageo"))
      (libsource (lib "Jaden_Lib") (part "RES-0603"))
    )
    (comp (ref "R94")
      (value "1K")
      (footprint "RES-0603")
      (description "Chip Resistor 0603(1608)")
      (fields (field (name "TOLERANCE") "1%") (field (name "MANUFACTURER") "Yageo"))
      (libsource (lib "Jaden_Lib") (part "RES-0603"))
    )
    (comp (ref "R95")
      (value "1K")
      (footprint "RES-0603")
      (description "Chip Resistor 0603(1608)")
      (fields (field (name "TOLERANCE") "1%") (field (name "MANUFACTURER") "Yageo"))
      (libsource (lib "Jaden_Lib") (part "RES-0603"))
    )
    (comp (ref "R96")
      (value "300R")
      (footprint "RES-0603")
      (description "Chip Resistor 0603(1608)")
      (fields (field (name "TOLERANCE") "1%") (field (name "MANUFACTURER") "Yageo"))
      (libsource (lib "Jaden_Lib") (part "RES-0603"))
    )
    (comp (ref "R97")
      (value "10K")
      (footprint "RES-0603")
      (description "Chip Resistor 0603(1608)")
      (fields (field (name "TOLERANCE") "1%") (field (name "MANUFACTURER") "Yageo"))
      (libsource (lib "Jaden_Lib") (part "RES-0603"))
    )
    (comp (ref "R98")
      (value "NC")
      (footprint "RES-0603")
      (description "Chip Resistor 0603(1608)")
      (fields (field (name "TOLERANCE") "1%") (field (name "MANUFACTURER") "Yageo"))
      (libsource (lib "Jaden_Lib") (part "RES-0603"))
    )
    (comp (ref "R99")
      (value "NC")
      (footprint "RES-0603")
      (description "Chip Resistor 0603(1608)")
      (fields (field (name "TOLERANCE") "1%") (field (name "MANUFACTURER") "Yageo"))
      (libsource (lib "Jaden_Lib") (part "RES-0603"))
    )
    (comp (ref "R100")
      (value "10K")
      (footprint "RES-0603")
      (description "Chip Resistor 0603(1608)")
      (fields (field (name "TOLERANCE") "1%") (field (name "MANUFACTURER") "Yageo"))
      (libsource (lib "Jaden_Lib") (part "RES-0603"))
    )
    (comp (ref "R101")
      (value "300R")
      (footprint "RES-0603")
      (description "Chip Resistor 0603(1608)")
      (fields (field (name "TOLERANCE") "1%") (field (name "MANUFACTURER") "Yageo"))
      (libsource (lib "Jaden_Lib") (part "RES-0603"))
    )
    (comp (ref "R102")
      (value "10K")
      (footprint "RES-0603")
      (description "Chip Resistor 0603(1608)")
      (fields (field (name "TOLERANCE") "1%") (field (name "MANUFACTURER") "Yageo"))
      (libsource (lib "Jaden_Lib") (part "RES-0603"))
    )
    (comp (ref "R103")
      (value "NC")
      (footprint "RES-0603")
      (description "Chip Resistor 0603(1608)")
      (fields (field (name "TOLERANCE") "1%") (field (name "MANUFACTURER") "Yageo"))
      (libsource (lib "Jaden_Lib") (part "RES-0603"))
    )
    (comp (ref "R104")
      (value "10K")
      (footprint "RES-0603")
      (description "Chip Resistor 0603(1608)")
      (fields (field (name "TOLERANCE") "1%") (field (name "MANUFACTURER") "Yageo"))
      (libsource (lib "Jaden_Lib") (part "RES-0603"))
    )
    (comp (ref "R105")
      (value "NC")
      (footprint "RES-0603")
      (description "Chip Resistor 0603(1608)")
      (fields (field (name "TOLERANCE") "1%") (field (name "MANUFACTURER") "Yageo"))
      (libsource (lib "Jaden_Lib") (part "RES-0603"))
    )
    (comp (ref "R106")
      (value "NC")
      (footprint "RES-0603")
      (description "Chip Resistor 0603(1608)")
      (fields (field (name "TOLERANCE") "1%") (field (name "MANUFACTURER") "Yageo"))
      (libsource (lib "Jaden_Lib") (part "RES-0603"))
    )
    (comp (ref "R107")
      (value "NC")
      (footprint "RES-0603")
      (description "Chip Resistor 0603(1608)")
      (fields (field (name "TOLERANCE") "1%") (field (name "MANUFACTURER") "Yageo"))
      (libsource (lib "Jaden_Lib") (part "RES-0603"))
    )
    (comp (ref "R108")
      (value "NC")
      (footprint "RES-0603")
      (description "Chip Resistor 0603(1608)")
      (fields (field (name "TOLERANCE") "1%") (field (name "MANUFACTURER") "Yageo"))
      (libsource (lib "Jaden_Lib") (part "RES-0603"))
    )
    (comp (ref "R109")
      (value "NC")
      (footprint "RES-0603")
      (description "Chip Resistor 0603(1608)")
      (fields (field (name "TOLERANCE") "1%") (field (name "MANUFACTURER") "Yageo"))
      (libsource (lib "Jaden_Lib") (part "RES-0603"))
    )
    (comp (ref "R110")
      (value "NC")
      (footprint "RES-0603")
      (description "Chip Resistor 0603(1608)")
      (fields (field (name "TOLERANCE") "1%") (field (name "MANUFACTURER") "Yageo"))
      (libsource (lib "Jaden_Lib") (part "RES-0603"))
    )
    (comp (ref "R111")
      (value "NC")
      (footprint "RES-0603")
      (description "Chip Resistor 0603(1608)")
      (fields (field (name "TOLERANCE") "1%") (field (name "MANUFACTURER") "Yageo"))
      (libsource (lib "Jaden_Lib") (part "RES-0603"))
    )
    (comp (ref "R112")
      (value "NC")
      (footprint "RES-0603")
      (description "Chip Resistor 0603(1608)")
      (fields (field (name "TOLERANCE") "1%") (field (name "MANUFACTURER") "Yageo"))
      (libsource (lib "Jaden_Lib") (part "RES-0603"))
    )
    (comp (ref "R113")
      (value "NC")
      (footprint "RES-0603")
      (description "Chip Resistor 0603(1608)")
      (fields (field (name "TOLERANCE") "1%") (field (name "MANUFACTURER") "Yageo"))
      (libsource (lib "Jaden_Lib") (part "RES-0603"))
    )
    (comp (ref "SW1")
      (value "ITS-1107(SMD)")
      (footprint "IT-1107(SMD)")
      (description "TACT Switch (SMD)")
      (libsource (lib "Jaden_Lib") (part "ITS-1107(SMD)"))
    )
    (comp (ref "U1")
      (value "LM1117-3.3")
      (footprint "SOT-223")
      (description "800mA Low-Dropout Linear Regulator, 4-pin SOT-223, Pb-Free")
      (fields
        (field (name "PARTNUMBER") "LM1117IMP-3.3/NOPB")
        (field (name "MANUFACTURER") "Texas Instruments")
      )
      (libsource (lib "Jaden_Lib") (part "LM1117"))
    )
  )
  (nets
    (net (code "1") (name "/I2C1_SCL") (class "Default")
      (node (ref "J1") (pin "9") (pinfunction "9_9") (pintype "passive"))
      (node (ref "J10") (pin "9") (pinfunction "9_9") (pintype "passive"))
      (node (ref "J2") (pin "9") (pinfunction "9_9") (pintype "passive"))
      (node (ref "J3") (pin "9") (pinfunction "9_9") (pintype "passive"))
      (node (ref "J4") (pin "9") (pinfunction "9_9") (pintype "passive"))
      (node (ref "J5") (pin "9") (pinfunction "9_9") (pintype "passive"))
      (node (ref "J6") (pin "9") (pinfunction "9_9") (pintype "passive"))
      (node (ref "J7") (pin "9") (pinfunction "9_9") (pintype "passive"))
      (node (ref "J8") (pin "9") (pinfunction "9_9") (pintype "passive"))
      (node (ref "J9") (pin "9") (pinfunction "9_9") (pintype "passive"))
    )
    (net (code "2") (name "/I2C1_SDA") (class "Default")
      (node (ref "J1") (pin "10") (pinfunction "10_10") (pintype "passive"))
      (node (ref "J10") (pin "10") (pinfunction "10_10") (pintype "passive"))
      (node (ref "J2") (pin "10") (pinfunction "10_10") (pintype "passive"))
      (node (ref "J3") (pin "10") (pinfunction "10_10") (pintype "passive"))
      (node (ref "J4") (pin "10") (pinfunction "10_10") (pintype "passive"))
      (node (ref "J5") (pin "10") (pinfunction "10_10") (pintype "passive"))
      (node (ref "J6") (pin "10") (pinfunction "10_10") (pintype "passive"))
      (node (ref "J7") (pin "10") (pinfunction "10_10") (pintype "passive"))
      (node (ref "J8") (pin "10") (pinfunction "10_10") (pintype "passive"))
      (node (ref "J9") (pin "10") (pinfunction "10_10") (pintype "passive"))
    )
    (net (code "3") (name "/LCD_CS") (class "Default")
      (node (ref "P1") (pin "3") (pinfunction "3_3") (pintype "passive"))
      (node (ref "R91") (pin "1") (pinfunction "1_1") (pintype "passive"))
    )
    (net (code "4") (name "/LCD_DC") (class "Default")
      (node (ref "P1") (pin "5") (pinfunction "5_5") (pintype "passive"))
    )
    (net (code "5") (name "/LCD_LED") (class "Default")
      (node (ref "P1") (pin "8") (pinfunction "8_8") (pintype "passive"))
    )
    (net (code "6") (name "/LCD_MISO") (class "Default")
      (node (ref "P1") (pin "9") (pinfunction "9_9") (pintype "passive"))
    )
    (net (code "7") (name "/LCD_MOSI") (class "Default")
      (node (ref "P1") (pin "6") (pinfunction "6_6") (pintype "passive"))
    )
    (net (code "8") (name "/LCD_RESET") (class "Default")
      (node (ref "P1") (pin "4") (pinfunction "4_4") (pintype "passive"))
      (node (ref "R92") (pin "1") (pinfunction "1_1") (pintype "passive"))
    )
    (net (code "9") (name "/LCD_SCK") (class "Default")
      (node (ref "P1") (pin "7") (pinfunction "7_7") (pintype "passive"))
    )
    (net (code "10") (name "/RST") (class "Default")
      (node (ref "R49") (pin "1") (pinfunction "1_1") (pintype "passive"))
      (node (ref "R5") (pin "1") (pinfunction "1_1") (pintype "passive"))
      (node (ref "R50") (pin "1") (pinfunction "1_1") (pintype "passive"))
      (node (ref "R51") (pin "1") (pinfunction "1_1") (pintype "passive"))
      (node (ref "R52") (pin "1") (pinfunction "1_1") (pintype "passive"))
      (node (ref "R6") (pin "1") (pinfunction "1_1") (pintype "passive"))
      (node (ref "R7") (pin "1") (pinfunction "1_1") (pintype "passive"))
      (node (ref "R8") (pin "1") (pinfunction "1_1") (pintype "passive"))
      (node (ref "R94") (pin "1") (pinfunction "1_1") (pintype "passive"))
      (node (ref "R95") (pin "1") (pinfunction "1_1") (pintype "passive"))
      (node (ref "SW1") (pin "1") (pintype "passive"))
    )
    (net (code "11") (name "5V") (class "Default")
      (node (ref "D1") (pin "1") (pinfunction "A_1") (pintype "passive"))
      (node (ref "D10") (pin "1") (pinfunction "A_1") (pintype "passive"))
      (node (ref "D2") (pin "1") (pinfunction "A_1") (pintype "passive"))
      (node (ref "D3") (pin "1") (pinfunction "A_1") (pintype "passive"))
      (node (ref "D4") (pin "1") (pinfunction "A_1") (pintype "passive"))
      (node (ref "D5") (pin "1") (pinfunction "A_1") (pintype "passive"))
      (node (ref "D6") (pin "1") (pinfunction "A_1") (pintype "passive"))
      (node (ref "D7") (pin "1") (pinfunction "A_1") (pintype "passive"))
      (node (ref "D8") (pin "1") (pinfunction "A_1") (pintype "passive"))
      (node (ref "D9") (pin "1") (pinfunction "A_1") (pintype "passive"))
      (node (ref "R1") (pin "1") (pinfunction "1_1") (pintype "passive"))
      (node (ref "R2") (pin "1") (pinfunction "1_1") (pintype "passive"))
      (node (ref "R3") (pin "1") (pinfunction "1_1") (pintype "passive"))
      (node (ref "R4") (pin "1") (pinfunction "1_1") (pintype "passive"))
      (node (ref "R45") (pin "1") (pinfunction "1_1") (pintype "passive"))
      (node (ref "R46") (pin "1") (pinfunction "1_1") (pintype "passive"))
      (node (ref "R47") (pin "1") (pinfunction "1_1") (pintype "passive"))
      (node (ref "R48") (pin "1") (pinfunction "1_1") (pintype "passive"))
      (node (ref "R89") (pin "1") (pinfunction "1_1") (pintype "passive"))
      (node (ref "R90") (pin "1") (pinfunction "1_1") (pintype "passive"))
    )
    (net (code "12") (name "GND") (class "Default")
      (node (ref "C1") (pin "1") (pinfunction "1_1") (pintype "passive"))
      (node (ref "C2") (pin "1") (pinfunction "1_1") (pintype "passive"))
      (node (ref "C3") (pin "1") (pinfunction "1_1") (pintype "passive"))
      (node (ref "J1") (pin "13") (pinfunction "13_13") (pintype "passive"))
      (node (ref "J1") (pin "18") (pinfunction "18_18") (pintype "passive"))
      (node (ref "J1") (pin "3") (pinfunction "3_3") (pintype "passive"))
      (node (ref "J1") (pin "8") (pinfunction "8_8") (pintype "passive"))
      (node (ref "J10") (pin "13") (pinfunction "13_13") (pintype "passive"))
      (node (ref "J10") (pin "18") (pinfunction "18_18") (pintype "passive"))
      (node (ref "J10") (pin "3") (pinfunction "3_3") (pintype "passive"))
      (node (ref "J10") (pin "8") (pinfunction "8_8") (pintype "passive"))
      (node (ref "J2") (pin "13") (pinfunction "13_13") (pintype "passive"))
      (node (ref "J2") (pin "18") (pinfunction "18_18") (pintype "passive"))
      (node (ref "J2") (pin "3") (pinfunction "3_3") (pintype "passive"))
      (node (ref "J2") (pin "8") (pinfunction "8_8") (pintype "passive"))
      (node (ref "J3") (pin "13") (pinfunction "13_13") (pintype "passive"))
      (node (ref "J3") (pin "18") (pinfunction "18_18") (pintype "passive"))
      (node (ref "J3") (pin "3") (pinfunction "3_3") (pintype "passive"))
      (node (ref "J3") (pin "8") (pinfunction "8_8") (pintype "passive"))
      (node (ref "J4") (pin "13") (pinfunction "13_13") (pintype "passive"))
      (node (ref "J4") (pin "18") (pinfunction "18_18") (pintype "passive"))
      (node (ref "J4") (pin "3") (pinfunction "3_3") (pintype "passive"))
      (node (ref "J4") (pin "8") (pinfunction "8_8") (pintype "passive"))
      (node (ref "J5") (pin "13") (pinfunction "13_13") (pintype "passive"))
      (node (ref "J5") (pin "18") (pinfunction "18_18") (pintype "passive"))
      (node (ref "J5") (pin "3") (pinfunction "3_3") (pintype "passive"))
      (node (ref "J5") (pin "8") (pinfunction "8_8") (pintype "passive"))
      (node (ref "J6") (pin "13") (pinfunction "13_13") (pintype "passive"))
      (node (ref "J6") (pin "18") (pinfunction "18_18") (pintype "passive"))
      (node (ref "J6") (pin "3") (pinfunction "3_3") (pintype "passive"))
      (node (ref "J6") (pin "8") (pinfunction "8_8") (pintype "passive"))
      (node (ref "J7") (pin "13") (pinfunction "13_13") (pintype "passive"))
      (node (ref "J7") (pin "18") (pinfunction "18_18") (pintype "passive"))
      (node (ref "J7") (pin "3") (pinfunction "3_3") (pintype "passive"))
      (node (ref "J7") (pin "8") (pinfunction "8_8") (pintype "passive"))
      (node (ref "J8") (pin "13") (pinfunction "13_13") (pintype "passive"))
      (node (ref "J8") (pin "18") (pinfunction "18_18") (pintype "passive"))
      (node (ref "J8") (pin "3") (pinfunction "3_3") (pintype "passive"))
      (node (ref "J8") (pin "8") (pinfunction "8_8") (pintype "passive"))
      (node (ref "J9") (pin "13") (pinfunction "13_13") (pintype "passive"))
      (node (ref "J9") (pin "18") (pinfunction "18_18") (pintype "passive"))
      (node (ref "J9") (pin "3") (pinfunction "3_3") (pintype "passive"))
      (node (ref "J9") (pin "8") (pinfunction "8_8") (pintype "passive"))
      (node (ref "P1") (pin "2") (pinfunction "2_2") (pintype "passive"))
      (node (ref "R106") (pin "1") (pinfunction "1_1") (pintype "passive"))
      (node (ref "R107") (pin "1") (pinfunction "1_1") (pintype "passive"))
      (node (ref "R108") (pin "1") (pinfunction "1_1") (pintype "passive"))
      (node (ref "R109") (pin "1") (pinfunction "1_1") (pintype "passive"))
      (node (ref "R110") (pin "1") (pinfunction "1_1") (pintype "passive"))
      (node (ref "R111") (pin "1") (pinfunction "1_1") (pintype "passive"))
      (node (ref "R112") (pin "1") (pinfunction "1_1") (pintype "passive"))
      (node (ref "R113") (pin "1") (pinfunction "1_1") (pintype "passive"))
      (node (ref "R29") (pin "1") (pinfunction "1_1") (pintype "passive"))
      (node (ref "R30") (pin "1") (pinfunction "1_1") (pintype "passive"))
      (node (ref "R31") (pin "1") (pinfunction "1_1") (pintype "passive"))
      (node (ref "R32") (pin "1") (pinfunction "1_1") (pintype "passive"))
      (node (ref "R33") (pin "1") (pinfunction "1_1") (pintype "passive"))
      (node (ref "R34") (pin "1") (pinfunction "1_1") (pintype "passive"))
      (node (ref "R35") (pin "1") (pinfunction "1_1") (pintype "passive"))
      (node (ref "R36") (pin "1") (pinfunction "1_1") (pintype "passive"))
      (node (ref "R37") (pin "1") (pinfunction "1_1") (pintype "passive"))
      (node (ref "R38") (pin "1") (pinfunction "1_1") (pintype "passive"))
      (node (ref "R39") (pin "1") (pinfunction "1_1") (pintype "passive"))
      (node (ref "R40") (pin "1") (pinfunction "1_1") (pintype "passive"))
      (node (ref "R41") (pin "1") (pinfunction "1_1") (pintype "passive"))
      (node (ref "R42") (pin "1") (pinfunction "1_1") (pintype "passive"))
      (node (ref "R43") (pin "1") (pinfunction "1_1") (pintype "passive"))
      (node (ref "R44") (pin "1") (pinfunction "1_1") (pintype "passive"))
      (node (ref "R73") (pin "1") (pinfunction "1_1") (pintype "passive"))
      (node (ref "R74") (pin "1") (pinfunction "1_1") (pintype "passive"))
      (node (ref "R75") (pin "1") (pinfunction "1_1") (pintype "passive"))
      (node (ref "R76") (pin "1") (pinfunction "1_1") (pintype "passive"))
      (node (ref "R77") (pin "1") (pinfunction "1_1") (pintype "passive"))
      (node (ref "R78") (pin "1") (pinfunction "1_1") (pintype "passive"))
      (node (ref "R79") (pin "1") (pinfunction "1_1") (pintype "passive"))
      (node (ref "R80") (pin "1") (pinfunction "1_1") (pintype "passive"))
      (node (ref "R81") (pin "1") (pinfunction "1_1") (pintype "passive"))
      (node (ref "R82") (pin "1") (pinfunction "1_1") (pintype "passive"))
      (node (ref "R83") (pin "1") (pinfunction "1_1") (pintype "passive"))
      (node (ref "R84") (pin "1") (pinfunction "1_1") (pintype "passive"))
      (node (ref "R85") (pin "1") (pinfunction "1_1") (pintype "passive"))
      (node (ref "R86") (pin "1") (pinfunction "1_1") (pintype "passive"))
      (node (ref "R87") (pin "1") (pinfunction "1_1") (pintype "passive"))
      (node (ref "R88") (pin "1") (pinfunction "1_1") (pintype "passive"))
      (node (ref "SW1") (pin "2") (pintype "passive"))
      (node (ref "U1") (pin "1") (pinfunction "GND_1") (pintype "power_in"))
    )
    (net (code "13") (name "LCD_3V3") (class "Default")
      (node (ref "C2") (pin "2") (pinfunction "2_2") (pintype "passive"))
      (node (ref "C3") (pin "2") (pinfunction "2_2") (pintype "passive"))
      (node (ref "P1") (pin "1") (pinfunction "1_1") (pintype "passive"))
      (node (ref "R91") (pin "2") (pinfunction "2_2") (pintype "passive"))
      (node (ref "R92") (pin "2") (pinfunction "2_2") (pintype "passive"))
      (node (ref "U1") (pin "2") (pinfunction "OUT_2") (pintype "power_in"))
      (node (ref "U1") (pin "4") (pinfunction "TAB_4") (pintype "power_in"))
    )
    (net (code "14") (name "Net-(D1-C)") (class "Default")
      (node (ref "D1") (pin "2") (pinfunction "C_2") (pintype "passive"))
      (node (ref "J1") (pin "2") (pinfunction "2_2") (pintype "passive"))
    )
    (net (code "15") (name "Net-(D2-C)") (class "Default")
      (node (ref "D2") (pin "2") (pinfunction "C_2") (pintype "passive"))
      (node (ref "J2") (pin "2") (pinfunction "2_2") (pintype "passive"))
    )
    (net (code "16") (name "Net-(D3-C)") (class "Default")
      (node (ref "D3") (pin "2") (pinfunction "C_2") (pintype "passive"))
      (node (ref "J3") (pin "2") (pinfunction "2_2") (pintype "passive"))
    )
    (net (code "17") (name "Net-(D4-C)") (class "Default")
      (node (ref "D4") (pin "2") (pinfunction "C_2") (pintype "passive"))
      (node (ref "J4") (pin "2") (pinfunction "2_2") (pintype "passive"))
    )
    (net (code "18") (name "Net-(D5-C)") (class "Default")
      (node (ref "D5") (pin "2") (pinfunction "C_2") (pintype "passive"))
      (node (ref "J5") (pin "2") (pinfunction "2_2") (pintype "passive"))
    )
    (net (code "19") (name "Net-(D6-C)") (class "Default")
      (node (ref "D6") (pin "2") (pinfunction "C_2") (pintype "passive"))
      (node (ref "J6") (pin "2") (pinfunction "2_2") (pintype "passive"))
    )
    (net (code "20") (name "Net-(D7-C)") (class "Default")
      (node (ref "D7") (pin "2") (pinfunction "C_2") (pintype "passive"))
      (node (ref "J7") (pin "2") (pinfunction "2_2") (pintype "passive"))
    )
    (net (code "21") (name "Net-(D8-C)") (class "Default")
      (node (ref "D8") (pin "2") (pinfunction "C_2") (pintype "passive"))
      (node (ref "J8") (pin "2") (pinfunction "2_2") (pintype "passive"))
    )
    (net (code "22") (name "Net-(D9-C)") (class "Default")
      (node (ref "D9") (pin "2") (pinfunction "C_2") (pintype "passive"))
      (node (ref "J9") (pin "2") (pinfunction "2_2") (pintype "passive"))
    )
    (net (code "23") (name "Net-(D10-C)") (class "Default")
      (node (ref "D10") (pin "2") (pinfunction "C_2") (pintype "passive"))
      (node (ref "J10") (pin "2") (pinfunction "2_2") (pintype "passive"))
    )
    (net (code "24") (name "Net-(J1-Pad11)") (class "Default")
      (node (ref "J1") (pin "11") (pinfunction "11_11") (pintype "passive"))
      (node (ref "R5") (pin "2") (pinfunction "2_2") (pintype "passive"))
    )
    (net (code "25") (name "Net-(J1-Pad15)") (class "Default")
      (node (ref "J1") (pin "15") (pinfunction "15_15") (pintype "passive"))
      (node (ref "R9") (pin "2") (pinfunction "2_2") (pintype "passive"))
    )
    (net (code "26") (name "Net-(J1-Pad16)") (class "Default")
      (node (ref "J1") (pin "16") (pinfunction "16_16") (pintype "passive"))
      (node (ref "R13") (pin "1") (pinfunction "1_1") (pintype "passive"))
      (node (ref "R32") (pin "2") (pinfunction "2_2") (pintype "passive"))
    )
    (net (code "27") (name "Net-(J1-Pad17)") (class "Default")
      (node (ref "J1") (pin "17") (pinfunction "17_17") (pintype "passive"))
      (node (ref "R12") (pin "1") (pinfunction "1_1") (pintype "passive"))
      (node (ref "R31") (pin "2") (pinfunction "2_2") (pintype "passive"))
    )
    (net (code "28") (name "Net-(J1-Pad19)") (class "Default")
      (node (ref "J1") (pin "19") (pinfunction "19_19") (pintype "passive"))
      (node (ref "R11") (pin "1") (pinfunction "1_1") (pintype "passive"))
      (node (ref "R30") (pin "2") (pinfunction "2_2") (pintype "passive"))
    )
    (net (code "29") (name "Net-(J1-Pad20)") (class "Default")
      (node (ref "J1") (pin "20") (pinfunction "20_20") (pintype "passive"))
      (node (ref "R10") (pin "1") (pinfunction "1_1") (pintype "passive"))
      (node (ref "R29") (pin "2") (pinfunction "2_2") (pintype "passive"))
    )
    (net (code "30") (name "Net-(J2-Pad11)") (class "Default")
      (node (ref "J2") (pin "11") (pinfunction "11_11") (pintype "passive"))
      (node (ref "R6") (pin "2") (pinfunction "2_2") (pintype "passive"))
    )
    (net (code "31") (name "Net-(J2-Pad15)") (class "Default")
      (node (ref "J2") (pin "15") (pinfunction "15_15") (pintype "passive"))
      (node (ref "R14") (pin "2") (pinfunction "2_2") (pintype "passive"))
    )
    (net (code "32") (name "Net-(J2-Pad16)") (class "Default")
      (node (ref "J2") (pin "16") (pinfunction "16_16") (pintype "passive"))
      (node (ref "R18") (pin "1") (pinfunction "1_1") (pintype "passive"))
      (node (ref "R36") (pin "2") (pinfunction "2_2") (pintype "passive"))
    )
    (net (code "33") (name "Net-(J2-Pad17)") (class "Default")
      (node (ref "J2") (pin "17") (pinfunction "17_17") (pintype "passive"))
      (node (ref "R17") (pin "1") (pinfunction "1_1") (pintype "passive"))
      (node (ref "R35") (pin "2") (pinfunction "2_2") (pintype "passive"))
    )
    (net (code "34") (name "Net-(J2-Pad19)") (class "Default")
      (node (ref "J2") (pin "19") (pinfunction "19_19") (pintype "passive"))
      (node (ref "R16") (pin "1") (pinfunction "1_1") (pintype "passive"))
      (node (ref "R34") (pin "2") (pinfunction "2_2") (pintype "passive"))
    )
    (net (code "35") (name "Net-(J2-Pad20)") (class "Default")
      (node (ref "J2") (pin "20") (pinfunction "20_20") (pintype "passive"))
      (node (ref "R15") (pin "1") (pinfunction "1_1") (pintype "passive"))
      (node (ref "R33") (pin "2") (pinfunction "2_2") (pintype "passive"))
    )
    (net (code "36") (name "Net-(J3-Pad11)") (class "Default")
      (node (ref "J3") (pin "11") (pinfunction "11_11") (pintype "passive"))
      (node (ref "R7") (pin "2") (pinfunction "2_2") (pintype "passive"))
    )
    (net (code "37") (name "Net-(J3-Pad15)") (class "Default")
      (node (ref "J3") (pin "15") (pinfunction "15_15") (pintype "passive"))
      (node (ref "R19") (pin "2") (pinfunction "2_2") (pintype "passive"))
    )
    (net (code "38") (name "Net-(J3-Pad16)") (class "Default")
      (node (ref "J3") (pin "16") (pinfunction "16_16") (pintype "passive"))
      (node (ref "R23") (pin "1") (pinfunction "1_1") (pintype "passive"))
      (node (ref "R40") (pin "2") (pinfunction "2_2") (pintype "passive"))
    )
    (net (code "39") (name "Net-(J3-Pad17)") (class "Default")
      (node (ref "J3") (pin "17") (pinfunction "17_17") (pintype "passive"))
      (node (ref "R22") (pin "1") (pinfunction "1_1") (pintype "passive"))
      (node (ref "R39") (pin "2") (pinfunction "2_2") (pintype "passive"))
    )
    (net (code "40") (name "Net-(J3-Pad19)") (class "Default")
      (node (ref "J3") (pin "19") (pinfunction "19_19") (pintype "passive"))
      (node (ref "R21") (pin "1") (pinfunction "1_1") (pintype "passive"))
      (node (ref "R38") (pin "2") (pinfunction "2_2") (pintype "passive"))
    )
    (net (code "41") (name "Net-(J3-Pad20)") (class "Default")
      (node (ref "J3") (pin "20") (pinfunction "20_20") (pintype "passive"))
      (node (ref "R20") (pin "1") (pinfunction "1_1") (pintype "passive"))
      (node (ref "R37") (pin "2") (pinfunction "2_2") (pintype "passive"))
    )
    (net (code "42") (name "Net-(J4-Pad11)") (class "Default")
      (node (ref "J4") (pin "11") (pinfunction "11_11") (pintype "passive"))
      (node (ref "R8") (pin "2") (pinfunction "2_2") (pintype "passive"))
    )
    (net (code "43") (name "Net-(J4-Pad15)") (class "Default")
      (node (ref "J4") (pin "15") (pinfunction "15_15") (pintype "passive"))
      (node (ref "R24") (pin "2") (pinfunction "2_2") (pintype "passive"))
    )
    (net (code "44") (name "Net-(J4-Pad16)") (class "Default")
      (node (ref "J4") (pin "16") (pinfunction "16_16") (pintype "passive"))
      (node (ref "R28") (pin "1") (pinfunction "1_1") (pintype "passive"))
      (node (ref "R44") (pin "2") (pinfunction "2_2") (pintype "passive"))
    )
    (net (code "45") (name "Net-(J4-Pad17)") (class "Default")
      (node (ref "J4") (pin "17") (pinfunction "17_17") (pintype "passive"))
      (node (ref "R27") (pin "1") (pinfunction "1_1") (pintype "passive"))
      (node (ref "R43") (pin "2") (pinfunction "2_2") (pintype "passive"))
    )
    (net (code "46") (name "Net-(J4-Pad19)") (class "Default")
      (node (ref "J4") (pin "19") (pinfunction "19_19") (pintype "passive"))
      (node (ref "R26") (pin "1") (pinfunction "1_1") (pintype "passive"))
      (node (ref "R42") (pin "2") (pinfunction "2_2") (pintype "passive"))
    )
    (net (code "47") (name "Net-(J4-Pad20)") (class "Default")
      (node (ref "J4") (pin "20") (pinfunction "20_20") (pintype "passive"))
      (node (ref "R25") (pin "1") (pinfunction "1_1") (pintype "passive"))
      (node (ref "R41") (pin "2") (pinfunction "2_2") (pintype "passive"))
    )
    (net (code "48") (name "Net-(J5-Pad11)") (class "Default")
      (node (ref "J5") (pin "11") (pinfunction "11_11") (pintype "passive"))
      (node (ref "R49") (pin "2") (pinfunction "2_2") (pintype "passive"))
    )
    (net (code "49") (name "Net-(J5-Pad15)") (class "Default")
      (node (ref "J5") (pin "15") (pinfunction "15_15") (pintype "passive"))
      (node (ref "R53") (pin "2") (pinfunction "2_2") (pintype "passive"))
    )
    (net (code "50") (name "Net-(J5-Pad16)") (class "Default")
      (node (ref "J5") (pin "16") (pinfunction "16_16") (pintype "passive"))
      (node (ref "R57") (pin "1") (pinfunction "1_1") (pintype "passive"))
      (node (ref "R76") (pin "2") (pinfunction "2_2") (pintype "passive"))
    )
    (net (code "51") (name "Net-(J5-Pad17)") (class "Default")
      (node (ref "J5") (pin "17") (pinfunction "17_17") (pintype "passive"))
      (node (ref "R56") (pin "1") (pinfunction "1_1") (pintype "passive"))
      (node (ref "R75") (pin "2") (pinfunction "2_2") (pintype "passive"))
    )
    (net (code "52") (name "Net-(J5-Pad19)") (class "Default")
      (node (ref "J5") (pin "19") (pinfunction "19_19") (pintype "passive"))
      (node (ref "R55") (pin "1") (pinfunction "1_1") (pintype "passive"))
      (node (ref "R74") (pin "2") (pinfunction "2_2") (pintype "passive"))
    )
    (net (code "53") (name "Net-(J5-Pad20)") (class "Default")
      (node (ref "J5") (pin "20") (pinfunction "20_20") (pintype "passive"))
      (node (ref "R54") (pin "1") (pinfunction "1_1") (pintype "passive"))
      (node (ref "R73") (pin "2") (pinfunction "2_2") (pintype "passive"))
    )
    (net (code "54") (name "Net-(J6-Pad11)") (class "Default")
      (node (ref "J6") (pin "11") (pinfunction "11_11") (pintype "passive"))
      (node (ref "R50") (pin "2") (pinfunction "2_2") (pintype "passive"))
    )
    (net (code "55") (name "Net-(J6-Pad15)") (class "Default")
      (node (ref "J6") (pin "15") (pinfunction "15_15") (pintype "passive"))
      (node (ref "R58") (pin "2") (pinfunction "2_2") (pintype "passive"))
    )
    (net (code "56") (name "Net-(J6-Pad16)") (class "Default")
      (node (ref "J6") (pin "16") (pinfunction "16_16") (pintype "passive"))
      (node (ref "R62") (pin "1") (pinfunction "1_1") (pintype "passive"))
      (node (ref "R80") (pin "2") (pinfunction "2_2") (pintype "passive"))
    )
    (net (code "57") (name "Net-(J6-Pad17)") (class "Default")
      (node (ref "J6") (pin "17") (pinfunction "17_17") (pintype "passive"))
      (node (ref "R61") (pin "1") (pinfunction "1_1") (pintype "passive"))
      (node (ref "R79") (pin "2") (pinfunction "2_2") (pintype "passive"))
    )
    (net (code "58") (name "Net-(J6-Pad19)") (class "Default")
      (node (ref "J6") (pin "19") (pinfunction "19_19") (pintype "passive"))
      (node (ref "R60") (pin "1") (pinfunction "1_1") (pintype "passive"))
      (node (ref "R78") (pin "2") (pinfunction "2_2") (pintype "passive"))
    )
    (net (code "59") (name "Net-(J6-Pad20)") (class "Default")
      (node (ref "J6") (pin "20") (pinfunction "20_20") (pintype "passive"))
      (node (ref "R59") (pin "1") (pinfunction "1_1") (pintype "passive"))
      (node (ref "R77") (pin "2") (pinfunction "2_2") (pintype "passive"))
    )
    (net (code "60") (name "Net-(J7-Pad11)") (class "Default")
      (node (ref "J7") (pin "11") (pinfunction "11_11") (pintype "passive"))
      (node (ref "R51") (pin "2") (pinfunction "2_2") (pintype "passive"))
    )
    (net (code "61") (name "Net-(J7-Pad15)") (class "Default")
      (node (ref "J7") (pin "15") (pinfunction "15_15") (pintype "passive"))
      (node (ref "R63") (pin "2") (pinfunction "2_2") (pintype "passive"))
    )
    (net (code "62") (name "Net-(J7-Pad16)") (class "Default")
      (node (ref "J7") (pin "16") (pinfunction "16_16") (pintype "passive"))
      (node (ref "R67") (pin "1") (pinfunction "1_1") (pintype "passive"))
      (node (ref "R84") (pin "2") (pinfunction "2_2") (pintype "passive"))
    )
    (net (code "63") (name "Net-(J7-Pad17)") (class "Default")
      (node (ref "J7") (pin "17") (pinfunction "17_17") (pintype "passive"))
      (node (ref "R66") (pin "1") (pinfunction "1_1") (pintype "passive"))
      (node (ref "R83") (pin "2") (pinfunction "2_2") (pintype "passive"))
    )
    (net (code "64") (name "Net-(J7-Pad19)") (class "Default")
      (node (ref "J7") (pin "19") (pinfunction "19_19") (pintype "passive"))
      (node (ref "R65") (pin "1") (pinfunction "1_1") (pintype "passive"))
      (node (ref "R82") (pin "2") (pinfunction "2_2") (pintype "passive"))
    )
    (net (code "65") (name "Net-(J7-Pad20)") (class "Default")
      (node (ref "J7") (pin "20") (pinfunction "20_20") (pintype "passive"))
      (node (ref "R64") (pin "1") (pinfunction "1_1") (pintype "passive"))
      (node (ref "R81") (pin "2") (pinfunction "2_2") (pintype "passive"))
    )
    (net (code "66") (name "Net-(J8-Pad11)") (class "Default")
      (node (ref "J8") (pin "11") (pinfunction "11_11") (pintype "passive"))
      (node (ref "R52") (pin "2") (pinfunction "2_2") (pintype "passive"))
    )
    (net (code "67") (name "Net-(J8-Pad15)") (class "Default")
      (node (ref "J8") (pin "15") (pinfunction "15_15") (pintype "passive"))
      (node (ref "R68") (pin "2") (pinfunction "2_2") (pintype "passive"))
    )
    (net (code "68") (name "Net-(J8-Pad16)") (class "Default")
      (node (ref "J8") (pin "16") (pinfunction "16_16") (pintype "passive"))
      (node (ref "R72") (pin "1") (pinfunction "1_1") (pintype "passive"))
      (node (ref "R88") (pin "2") (pinfunction "2_2") (pintype "passive"))
    )
    (net (code "69") (name "Net-(J8-Pad17)") (class "Default")
      (node (ref "J8") (pin "17") (pinfunction "17_17") (pintype "passive"))
      (node (ref "R71") (pin "1") (pinfunction "1_1") (pintype "passive"))
      (node (ref "R87") (pin "2") (pinfunction "2_2") (pintype "passive"))
    )
    (net (code "70") (name "Net-(J8-Pad19)") (class "Default")
      (node (ref "J8") (pin "19") (pinfunction "19_19") (pintype "passive"))
      (node (ref "R70") (pin "1") (pinfunction "1_1") (pintype "passive"))
      (node (ref "R86") (pin "2") (pinfunction "2_2") (pintype "passive"))
    )
    (net (code "71") (name "Net-(J8-Pad20)") (class "Default")
      (node (ref "J8") (pin "20") (pinfunction "20_20") (pintype "passive"))
      (node (ref "R69") (pin "1") (pinfunction "1_1") (pintype "passive"))
      (node (ref "R85") (pin "2") (pinfunction "2_2") (pintype "passive"))
    )
    (net (code "72") (name "Net-(J9-Pad11)") (class "Default")
      (node (ref "J9") (pin "11") (pinfunction "11_11") (pintype "passive"))
      (node (ref "R94") (pin "2") (pinfunction "2_2") (pintype "passive"))
    )
    (net (code "73") (name "Net-(J9-Pad15)") (class "Default")
      (node (ref "J9") (pin "15") (pinfunction "15_15") (pintype "passive"))
      (node (ref "R96") (pin "2") (pinfunction "2_2") (pintype "passive"))
    )
    (net (code "74") (name "Net-(J9-Pad16)") (class "Default")
      (node (ref "J9") (pin "16") (pinfunction "16_16") (pintype "passive"))
      (node (ref "R100") (pin "1") (pinfunction "1_1") (pintype "passive"))
      (node (ref "R109") (pin "2") (pinfunction "2_2") (pintype "passive"))
    )
    (net (code "75") (name "Net-(J9-Pad17)") (class "Default")
      (node (ref "J9") (pin "17") (pinfunction "17_17") (pintype "passive"))
      (node (ref "R108") (pin "2") (pinfunction "2_2") (pintype "passive"))
      (node (ref "R99") (pin "1") (pinfunction "1_1") (pintype "passive"))
    )
    (net (code "76") (name "Net-(J9-Pad19)") (class "Default")
      (node (ref "J9") (pin "19") (pinfunction "19_19") (pintype "passive"))
      (node (ref "R107") (pin "2") (pinfunction "2_2") (pintype "passive"))
      (node (ref "R98") (pin "1") (pinfunction "1_1") (pintype "passive"))
    )
    (net (code "77") (name "Net-(J9-Pad20)") (class "Default")
      (node (ref "J9") (pin "20") (pinfunction "20_20") (pintype "passive"))
      (node (ref "R106") (pin "2") (pinfunction "2_2") (pintype "passive"))
      (node (ref "R97") (pin "1") (pinfunction "1_1") (pintype "passive"))
    )
    (net (code "78") (name "Net-(J10-Pad11)") (class "Default")
      (node (ref "J10") (pin "11") (pinfunction "11_11") (pintype "passive"))
      (node (ref "R95") (pin "2") (pinfunction "2_2") (pintype "passive"))
    )
    (net (code "79") (name "Net-(J10-Pad15)") (class "Default")
      (node (ref "J10") (pin "15") (pinfunction "15_15") (pintype "passive"))
      (node (ref "R101") (pin "2") (pinfunction "2_2") (pintype "passive"))
    )
    (net (code "80") (name "Net-(J10-Pad16)") (class "Default")
      (node (ref "J10") (pin "16") (pinfunction "16_16") (pintype "passive"))
      (node (ref "R105") (pin "1") (pinfunction "1_1") (pintype "passive"))
      (node (ref "R113") (pin "2") (pinfunction "2_2") (pintype "passive"))
    )
    (net (code "81") (name "Net-(J10-Pad17)") (class "Default")
      (node (ref "J10") (pin "17") (pinfunction "17_17") (pintype "passive"))
      (node (ref "R104") (pin "1") (pinfunction "1_1") (pintype "passive"))
      (node (ref "R112") (pin "2") (pinfunction "2_2") (pintype "passive"))
    )
    (net (code "82") (name "Net-(J10-Pad19)") (class "Default")
      (node (ref "J10") (pin "19") (pinfunction "19_19") (pintype "passive"))
      (node (ref "R103") (pin "1") (pinfunction "1_1") (pintype "passive"))
      (node (ref "R111") (pin "2") (pinfunction "2_2") (pintype "passive"))
    )
    (net (code "83") (name "Net-(J10-Pad20)") (class "Default")
      (node (ref "J10") (pin "20") (pinfunction "20_20") (pintype "passive"))
      (node (ref "R102") (pin "1") (pinfunction "1_1") (pintype "passive"))
      (node (ref "R110") (pin "2") (pinfunction "2_2") (pintype "passive"))
    )
    (net (code "84") (name "Net-(LD1-A)") (class "Default")
      (node (ref "J1") (pin "5") (pinfunction "5_5") (pintype "passive"))
      (node (ref "LD1") (pin "1") (pinfunction "A_1") (pintype "passive"))
      (node (ref "R10") (pin "2") (pinfunction "2_2") (pintype "passive"))
      (node (ref "R11") (pin "2") (pinfunction "2_2") (pintype "passive"))
      (node (ref "R12") (pin "2") (pinfunction "2_2") (pintype "passive"))
      (node (ref "R13") (pin "2") (pinfunction "2_2") (pintype "passive"))
    )
    (net (code "85") (name "Net-(LD1-K)") (class "Default")
      (node (ref "LD1") (pin "2") (pinfunction "K_2") (pintype "passive"))
      (node (ref "R9") (pin "1") (pinfunction "1_1") (pintype "passive"))
    )
    (net (code "86") (name "Net-(LD2-A)") (class "Default")
      (node (ref "J2") (pin "5") (pinfunction "5_5") (pintype "passive"))
      (node (ref "LD2") (pin "1") (pinfunction "A_1") (pintype "passive"))
      (node (ref "R15") (pin "2") (pinfunction "2_2") (pintype "passive"))
      (node (ref "R16") (pin "2") (pinfunction "2_2") (pintype "passive"))
      (node (ref "R17") (pin "2") (pinfunction "2_2") (pintype "passive"))
      (node (ref "R18") (pin "2") (pinfunction "2_2") (pintype "passive"))
    )
    (net (code "87") (name "Net-(LD2-K)") (class "Default")
      (node (ref "LD2") (pin "2") (pinfunction "K_2") (pintype "passive"))
      (node (ref "R14") (pin "1") (pinfunction "1_1") (pintype "passive"))
    )
    (net (code "88") (name "Net-(LD3-A)") (class "Default")
      (node (ref "J3") (pin "5") (pinfunction "5_5") (pintype "passive"))
      (node (ref "LD3") (pin "1") (pinfunction "A_1") (pintype "passive"))
      (node (ref "R20") (pin "2") (pinfunction "2_2") (pintype "passive"))
      (node (ref "R21") (pin "2") (pinfunction "2_2") (pintype "passive"))
      (node (ref "R22") (pin "2") (pinfunction "2_2") (pintype "passive"))
      (node (ref "R23") (pin "2") (pinfunction "2_2") (pintype "passive"))
    )
    (net (code "89") (name "Net-(LD3-K)") (class "Default")
      (node (ref "LD3") (pin "2") (pinfunction "K_2") (pintype "passive"))
      (node (ref "R19") (pin "1") (pinfunction "1_1") (pintype "passive"))
    )
    (net (code "90") (name "Net-(LD4-A)") (class "Default")
      (node (ref "J4") (pin "5") (pinfunction "5_5") (pintype "passive"))
      (node (ref "LD4") (pin "1") (pinfunction "A_1") (pintype "passive"))
      (node (ref "R25") (pin "2") (pinfunction "2_2") (pintype "passive"))
      (node (ref "R26") (pin "2") (pinfunction "2_2") (pintype "passive"))
      (node (ref "R27") (pin "2") (pinfunction "2_2") (pintype "passive"))
      (node (ref "R28") (pin "2") (pinfunction "2_2") (pintype "passive"))
    )
    (net (code "91") (name "Net-(LD4-K)") (class "Default")
      (node (ref "LD4") (pin "2") (pinfunction "K_2") (pintype "passive"))
      (node (ref "R24") (pin "1") (pinfunction "1_1") (pintype "passive"))
    )
    (net (code "92") (name "Net-(LD5-A)") (class "Default")
      (node (ref "J5") (pin "5") (pinfunction "5_5") (pintype "passive"))
      (node (ref "LD5") (pin "1") (pinfunction "A_1") (pintype "passive"))
      (node (ref "R54") (pin "2") (pinfunction "2_2") (pintype "passive"))
      (node (ref "R55") (pin "2") (pinfunction "2_2") (pintype "passive"))
      (node (ref "R56") (pin "2") (pinfunction "2_2") (pintype "passive"))
      (node (ref "R57") (pin "2") (pinfunction "2_2") (pintype "passive"))
    )
    (net (code "93") (name "Net-(LD5-K)") (class "Default")
      (node (ref "LD5") (pin "2") (pinfunction "K_2") (pintype "passive"))
      (node (ref "R53") (pin "1") (pinfunction "1_1") (pintype "passive"))
    )
    (net (code "94") (name "Net-(LD6-A)") (class "Default")
      (node (ref "J6") (pin "5") (pinfunction "5_5") (pintype "passive"))
      (node (ref "LD6") (pin "1") (pinfunction "A_1") (pintype "passive"))
      (node (ref "R59") (pin "2") (pinfunction "2_2") (pintype "passive"))
      (node (ref "R60") (pin "2") (pinfunction "2_2") (pintype "passive"))
      (node (ref "R61") (pin "2") (pinfunction "2_2") (pintype "passive"))
      (node (ref "R62") (pin "2") (pinfunction "2_2") (pintype "passive"))
    )
    (net (code "95") (name "Net-(LD6-K)") (class "Default")
      (node (ref "LD6") (pin "2") (pinfunction "K_2") (pintype "passive"))
      (node (ref "R58") (pin "1") (pinfunction "1_1") (pintype "passive"))
    )
    (net (code "96") (name "Net-(LD7-A)") (class "Default")
      (node (ref "J7") (pin "5") (pinfunction "5_5") (pintype "passive"))
      (node (ref "LD7") (pin "1") (pinfunction "A_1") (pintype "passive"))
      (node (ref "R64") (pin "2") (pinfunction "2_2") (pintype "passive"))
      (node (ref "R65") (pin "2") (pinfunction "2_2") (pintype "passive"))
      (node (ref "R66") (pin "2") (pinfunction "2_2") (pintype "passive"))
      (node (ref "R67") (pin "2") (pinfunction "2_2") (pintype "passive"))
    )
    (net (code "97") (name "Net-(LD7-K)") (class "Default")
      (node (ref "LD7") (pin "2") (pinfunction "K_2") (pintype "passive"))
      (node (ref "R63") (pin "1") (pinfunction "1_1") (pintype "passive"))
    )
    (net (code "98") (name "Net-(LD8-A)") (class "Default")
      (node (ref "J8") (pin "5") (pinfunction "5_5") (pintype "passive"))
      (node (ref "LD8") (pin "1") (pinfunction "A_1") (pintype "passive"))
      (node (ref "R69") (pin "2") (pinfunction "2_2") (pintype "passive"))
      (node (ref "R70") (pin "2") (pinfunction "2_2") (pintype "passive"))
      (node (ref "R71") (pin "2") (pinfunction "2_2") (pintype "passive"))
      (node (ref "R72") (pin "2") (pinfunction "2_2") (pintype "passive"))
    )
    (net (code "99") (name "Net-(LD8-K)") (class "Default")
      (node (ref "LD8") (pin "2") (pinfunction "K_2") (pintype "passive"))
      (node (ref "R68") (pin "1") (pinfunction "1_1") (pintype "passive"))
    )
    (net (code "100") (name "Net-(LD9-A)") (class "Default")
      (node (ref "J9") (pin "5") (pinfunction "5_5") (pintype "passive"))
      (node (ref "LD9") (pin "1") (pinfunction "A_1") (pintype "passive"))
      (node (ref "R100") (pin "2") (pinfunction "2_2") (pintype "passive"))
      (node (ref "R97") (pin "2") (pinfunction "2_2") (pintype "passive"))
      (node (ref "R98") (pin "2") (pinfunction "2_2") (pintype "passive"))
      (node (ref "R99") (pin "2") (pinfunction "2_2") (pintype "passive"))
    )
    (net (code "101") (name "Net-(LD9-K)") (class "Default")
      (node (ref "LD9") (pin "2") (pinfunction "K_2") (pintype "passive"))
      (node (ref "R96") (pin "1") (pinfunction "1_1") (pintype "passive"))
    )
    (net (code "102") (name "Net-(LD10-A)") (class "Default")
      (node (ref "J10") (pin "5") (pinfunction "5_5") (pintype "passive"))
      (node (ref "LD10") (pin "1") (pinfunction "A_1") (pintype "passive"))
      (node (ref "R102") (pin "2") (pinfunction "2_2") (pintype "passive"))
      (node (ref "R103") (pin "2") (pinfunction "2_2") (pintype "passive"))
      (node (ref "R104") (pin "2") (pinfunction "2_2") (pintype "passive"))
      (node (ref "R105") (pin "2") (pinfunction "2_2") (pintype "passive"))
    )
    (net (code "103") (name "Net-(LD10-K)") (class "Default")
      (node (ref "LD10") (pin "2") (pinfunction "K_2") (pintype "passive"))
      (node (ref "R101") (pin "1") (pinfunction "1_1") (pintype "passive"))
    )
    (net (code "104") (name "VBUS") (class "Default")
      (node (ref "J1") (pin "1") (pinfunction "1_1") (pintype "passive"))
      (node (ref "J10") (pin "1") (pinfunction "1_1") (pintype "passive"))
      (node (ref "J2") (pin "1") (pinfunction "1_1") (pintype "passive"))
      (node (ref "J3") (pin "1") (pinfunction "1_1") (pintype "passive"))
      (node (ref "J4") (pin "1") (pinfunction "1_1") (pintype "passive"))
      (node (ref "J5") (pin "1") (pinfunction "1_1") (pintype "passive"))
      (node (ref "J6") (pin "1") (pinfunction "1_1") (pintype "passive"))
      (node (ref "J7") (pin "1") (pinfunction "1_1") (pintype "passive"))
      (node (ref "J8") (pin "1") (pinfunction "1_1") (pintype "passive"))
      (node (ref "J9") (pin "1") (pinfunction "1_1") (pintype "passive"))
      (node (ref "R1") (pin "2") (pinfunction "2_2") (pintype "passive"))
      (node (ref "R2") (pin "2") (pinfunction "2_2") (pintype "passive"))
      (node (ref "R3") (pin "2") (pinfunction "2_2") (pintype "passive"))
      (node (ref "R4") (pin "2") (pinfunction "2_2") (pintype "passive"))
      (node (ref "R45") (pin "2") (pinfunction "2_2") (pintype "passive"))
      (node (ref "R46") (pin "2") (pinfunction "2_2") (pintype "passive"))
      (node (ref "R47") (pin "2") (pinfunction "2_2") (pintype "passive"))
      (node (ref "R48") (pin "2") (pinfunction "2_2") (pintype "passive"))
      (node (ref "R89") (pin "2") (pinfunction "2_2") (pintype "passive"))
      (node (ref "R90") (pin "2") (pinfunction "2_2") (pintype "passive"))
    )
    (net (code "105") (name "VSYS") (class "Default")
      (node (ref "C1") (pin "2") (pinfunction "2_2") (pintype "passive"))
      (node (ref "U1") (pin "3") (pinfunction "IN_3") (pintype "power_in"))
    )
    (net (code "106") (name "unconnected-(J1-Pad4)") (class "Default")
      (node (ref "J1") (pin "4") (pinfunction "4_4") (pintype "passive+no_connect"))
    )
    (net (code "107") (name "unconnected-(J1-Pad6)") (class "Default")
      (node (ref "J1") (pin "6") (pinfunction "6_6") (pintype "passive+no_connect"))
    )
    (net (code "108") (name "unconnected-(J1-Pad7)") (class "Default")
      (node (ref "J1") (pin "7") (pinfunction "7_7") (pintype "passive+no_connect"))
    )
    (net (code "109") (name "unconnected-(J1-Pad12)") (class "Default")
      (node (ref "J1") (pin "12") (pinfunction "12_12") (pintype "passive+no_connect"))
    )
    (net (code "110") (name "unconnected-(J1-Pad14)") (class "Default")
      (node (ref "J1") (pin "14") (pinfunction "14_14") (pintype "passive+no_connect"))
    )
    (net (code "111") (name "unconnected-(J2-Pad4)") (class "Default")
      (node (ref "J2") (pin "4") (pinfunction "4_4") (pintype "passive+no_connect"))
    )
    (net (code "112") (name "unconnected-(J2-Pad6)") (class "Default")
      (node (ref "J2") (pin "6") (pinfunction "6_6") (pintype "passive+no_connect"))
    )
    (net (code "113") (name "unconnected-(J2-Pad7)") (class "Default")
      (node (ref "J2") (pin "7") (pinfunction "7_7") (pintype "passive+no_connect"))
    )
    (net (code "114") (name "unconnected-(J2-Pad12)") (class "Default")
      (node (ref "J2") (pin "12") (pinfunction "12_12") (pintype "passive+no_connect"))
    )
    (net (code "115") (name "unconnected-(J2-Pad14)") (class "Default")
      (node (ref "J2") (pin "14") (pinfunction "14_14") (pintype "passive+no_connect"))
    )
    (net (code "116") (name "unconnected-(J3-Pad4)") (class "Default")
      (node (ref "J3") (pin "4") (pinfunction "4_4") (pintype "passive+no_connect"))
    )
    (net (code "117") (name "unconnected-(J3-Pad6)") (class "Default")
      (node (ref "J3") (pin "6") (pinfunction "6_6") (pintype "passive+no_connect"))
    )
    (net (code "118") (name "unconnected-(J3-Pad7)") (class "Default")
      (node (ref "J3") (pin "7") (pinfunction "7_7") (pintype "passive+no_connect"))
    )
    (net (code "119") (name "unconnected-(J3-Pad12)") (class "Default")
      (node (ref "J3") (pin "12") (pinfunction "12_12") (pintype "passive+no_connect"))
    )
    (net (code "120") (name "unconnected-(J3-Pad14)") (class "Default")
      (node (ref "J3") (pin "14") (pinfunction "14_14") (pintype "passive+no_connect"))
    )
    (net (code "121") (name "unconnected-(J4-Pad4)") (class "Default")
      (node (ref "J4") (pin "4") (pinfunction "4_4") (pintype "passive+no_connect"))
    )
    (net (code "122") (name "unconnected-(J4-Pad6)") (class "Default")
      (node (ref "J4") (pin "6") (pinfunction "6_6") (pintype "passive+no_connect"))
    )
    (net (code "123") (name "unconnected-(J4-Pad7)") (class "Default")
      (node (ref "J4") (pin "7") (pinfunction "7_7") (pintype "passive+no_connect"))
    )
    (net (code "124") (name "unconnected-(J4-Pad12)") (class "Default")
      (node (ref "J4") (pin "12") (pinfunction "12_12") (pintype "passive+no_connect"))
    )
    (net (code "125") (name "unconnected-(J4-Pad14)") (class "Default")
      (node (ref "J4") (pin "14") (pinfunction "14_14") (pintype "passive+no_connect"))
    )
    (net (code "126") (name "unconnected-(J5-Pad4)") (class "Default")
      (node (ref "J5") (pin "4") (pinfunction "4_4") (pintype "passive+no_connect"))
    )
    (net (code "127") (name "unconnected-(J5-Pad6)") (class "Default")
      (node (ref "J5") (pin "6") (pinfunction "6_6") (pintype "passive+no_connect"))
    )
    (net (code "128") (name "unconnected-(J5-Pad7)") (class "Default")
      (node (ref "J5") (pin "7") (pinfunction "7_7") (pintype "passive+no_connect"))
    )
    (net (code "129") (name "unconnected-(J5-Pad12)") (class "Default")
      (node (ref "J5") (pin "12") (pinfunction "12_12") (pintype "passive"))
    )
    (net (code "130") (name "unconnected-(J5-Pad14)") (class "Default")
      (node (ref "J5") (pin "14") (pinfunction "14_14") (pintype "passive+no_connect"))
    )
    (net (code "131") (name "unconnected-(J6-Pad4)") (class "Default")
      (node (ref "J6") (pin "4") (pinfunction "4_4") (pintype "passive+no_connect"))
    )
    (net (code "132") (name "unconnected-(J6-Pad6)") (class "Default")
      (node (ref "J6") (pin "6") (pinfunction "6_6") (pintype "passive+no_connect"))
    )
    (net (code "133") (name "unconnected-(J6-Pad7)") (class "Default")
      (node (ref "J6") (pin "7") (pinfunction "7_7") (pintype "passive+no_connect"))
    )
    (net (code "134") (name "unconnected-(J6-Pad12)") (class "Default")
      (node (ref "J6") (pin "12") (pinfunction "12_12") (pintype "passive+no_connect"))
    )
    (net (code "135") (name "unconnected-(J6-Pad14)") (class "Default")
      (node (ref "J6") (pin "14") (pinfunction "14_14") (pintype "passive+no_connect"))
    )
    (net (code "136") (name "unconnected-(J7-Pad4)") (class "Default")
      (node (ref "J7") (pin "4") (pinfunction "4_4") (pintype "passive+no_connect"))
    )
    (net (code "137") (name "unconnected-(J7-Pad6)") (class "Default")
      (node (ref "J7") (pin "6") (pinfunction "6_6") (pintype "passive+no_connect"))
    )
    (net (code "138") (name "unconnected-(J7-Pad7)") (class "Default")
      (node (ref "J7") (pin "7") (pinfunction "7_7") (pintype "passive+no_connect"))
    )
    (net (code "139") (name "unconnected-(J7-Pad12)") (class "Default")
      (node (ref "J7") (pin "12") (pinfunction "12_12") (pintype "passive+no_connect"))
    )
    (net (code "140") (name "unconnected-(J7-Pad14)") (class "Default")
      (node (ref "J7") (pin "14") (pinfunction "14_14") (pintype "passive+no_connect"))
    )
    (net (code "141") (name "unconnected-(J8-Pad4)") (class "Default")
      (node (ref "J8") (pin "4") (pinfunction "4_4") (pintype "passive+no_connect"))
    )
    (net (code "142") (name "unconnected-(J8-Pad6)") (class "Default")
      (node (ref "J8") (pin "6") (pinfunction "6_6") (pintype "passive+no_connect"))
    )
    (net (code "143") (name "unconnected-(J8-Pad7)") (class "Default")
      (node (ref "J8") (pin "7") (pinfunction "7_7") (pintype "passive+no_connect"))
    )
    (net (code "144") (name "unconnected-(J8-Pad12)") (class "Default")
      (node (ref "J8") (pin "12") (pinfunction "12_12") (pintype "passive+no_connect"))
    )
    (net (code "145") (name "unconnected-(J8-Pad14)") (class "Default")
      (node (ref "J8") (pin "14") (pinfunction "14_14") (pintype "passive+no_connect"))
    )
    (net (code "146") (name "unconnected-(J9-Pad4)") (class "Default")
      (node (ref "J9") (pin "4") (pinfunction "4_4") (pintype "passive+no_connect"))
    )
    (net (code "147") (name "unconnected-(J9-Pad6)") (class "Default")
      (node (ref "J9") (pin "6") (pinfunction "6_6") (pintype "passive+no_connect"))
    )
    (net (code "148") (name "unconnected-(J9-Pad7)") (class "Default")
      (node (ref "J9") (pin "7") (pinfunction "7_7") (pintype "passive+no_connect"))
    )
    (net (code "149") (name "unconnected-(J9-Pad12)") (class "Default")
      (node (ref "J9") (pin "12") (pinfunction "12_12") (pintype "passive+no_connect"))
    )
    (net (code "150") (name "unconnected-(J9-Pad14)") (class "Default")
      (node (ref "J9") (pin "14") (pinfunction "14_14") (pintype "passive+no_connect"))
    )
    (net (code "151") (name "unconnected-(J10-Pad4)") (class "Default")
      (node (ref "J10") (pin "4") (pinfunction "4_4") (pintype "passive+no_connect"))
    )
    (net (code "152") (name "unconnected-(J10-Pad6)") (class "Default")
      (node (ref "J10") (pin "6") (pinfunction "6_6") (pintype "passive+no_connect"))
    )
    (net (code "153") (name "unconnected-(J10-Pad7)") (class "Default")
      (node (ref "J10") (pin "7") (pinfunction "7_7") (pintype "passive+no_connect"))
    )
    (net (code "154") (name "unconnected-(J10-Pad12)") (class "Default")
      (node (ref "J10") (pin "12") (pinfunction "12_12") (pintype "passive+no_connect"))
    )
    (net (code "155") (name "unconnected-(J10-Pad14)") (class "Default")
      (node (ref "J10") (pin "14") (pinfunction "14_14") (pintype "passive+no_connect"))
    )
  )
)
